# transistor_tester_V1_07_E3.net
KiCad netlist of a schematic drawn in Altium Designer
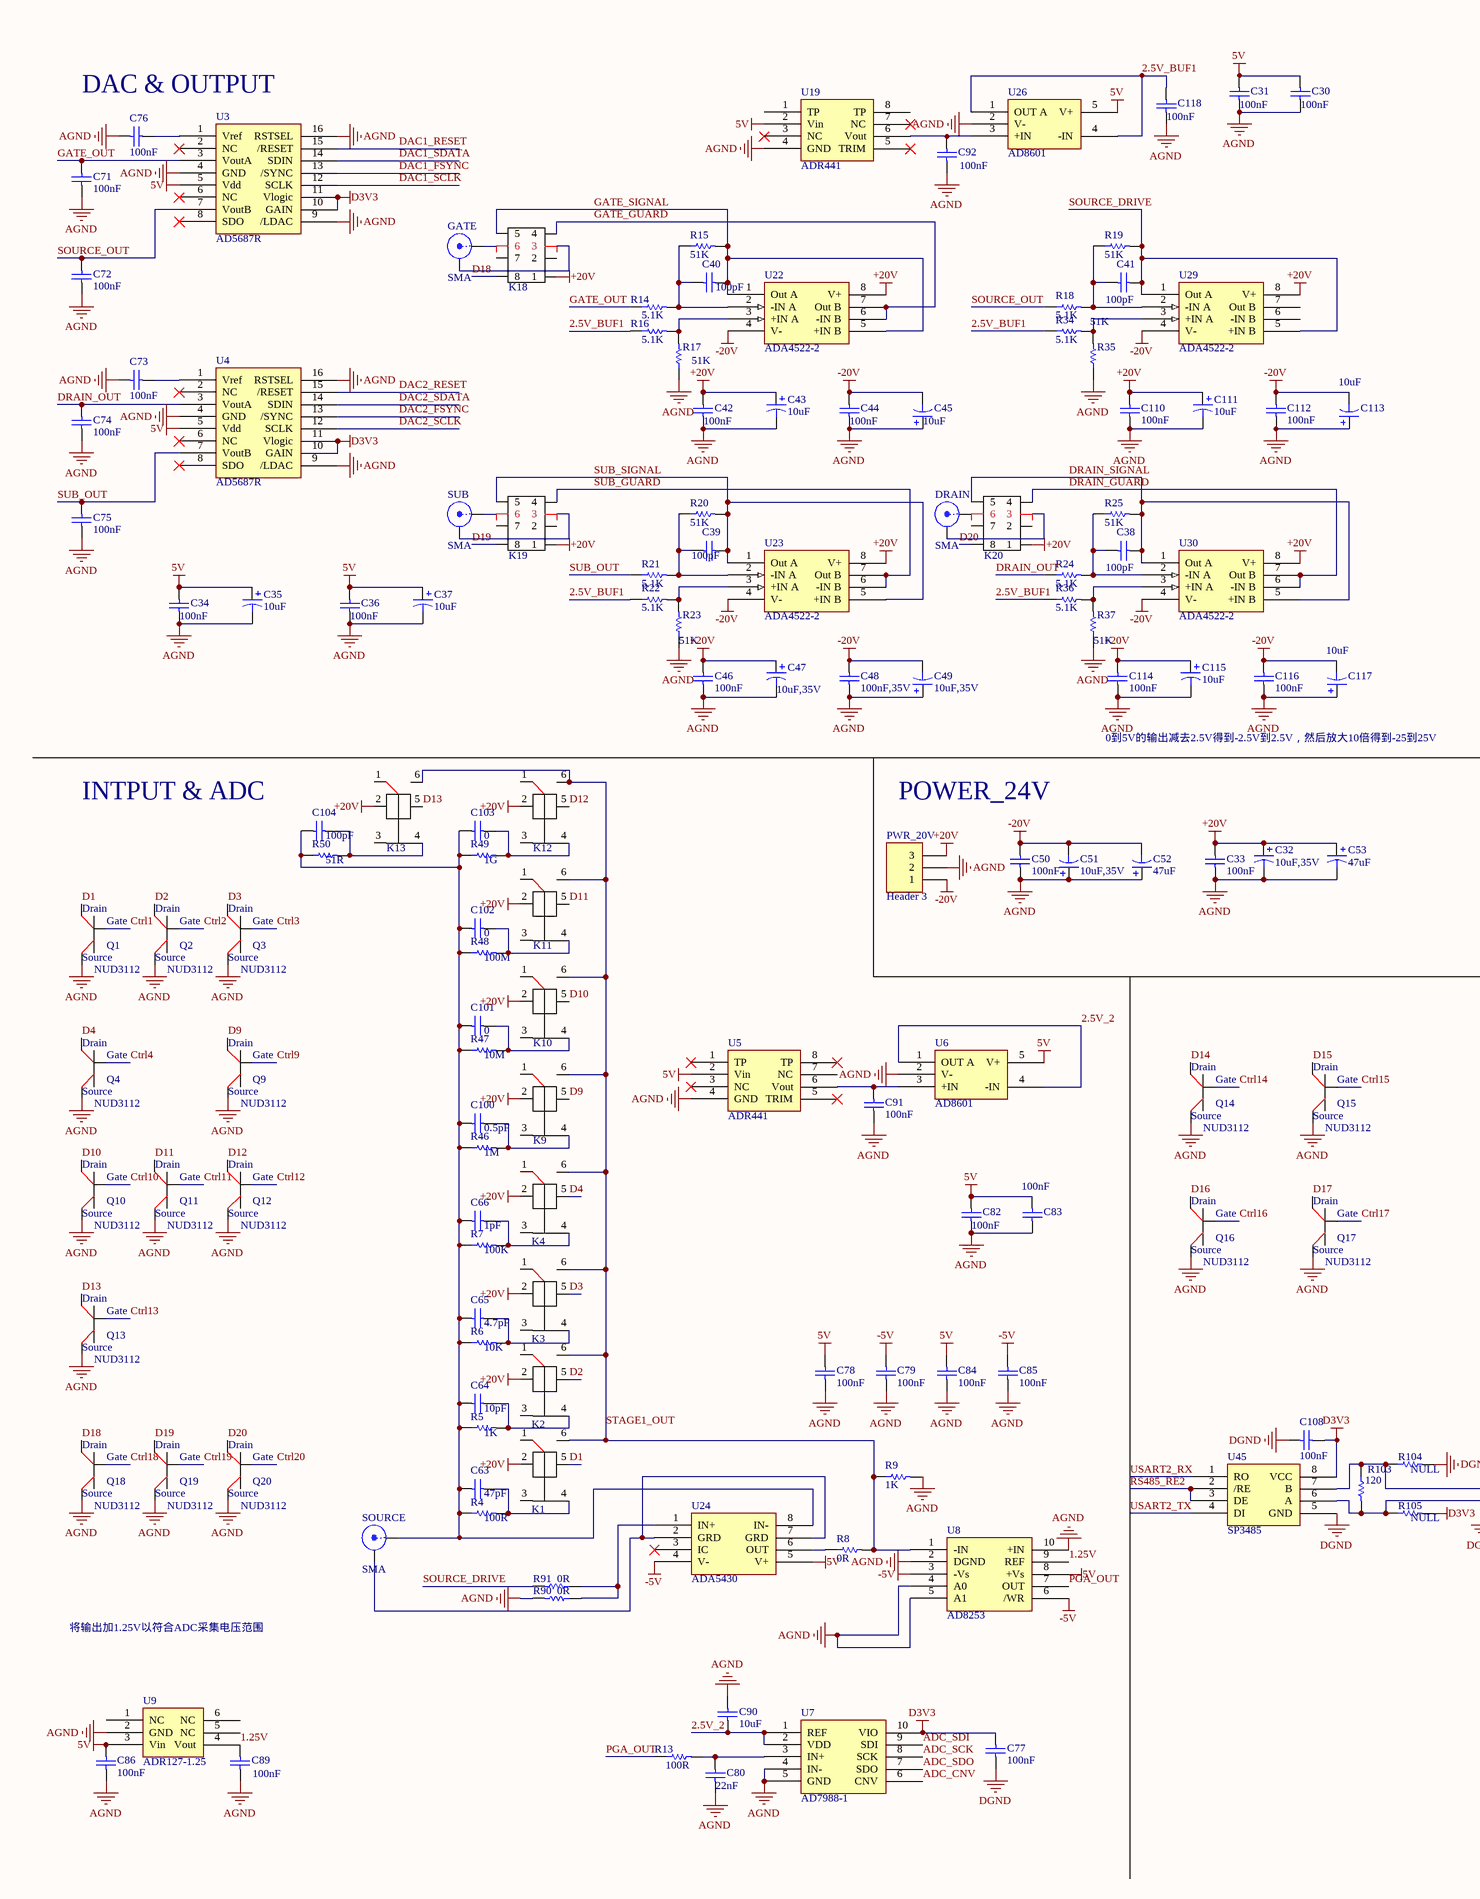
[diagram p0: transistor_tester_V1.07_E3.SchDoc, left]
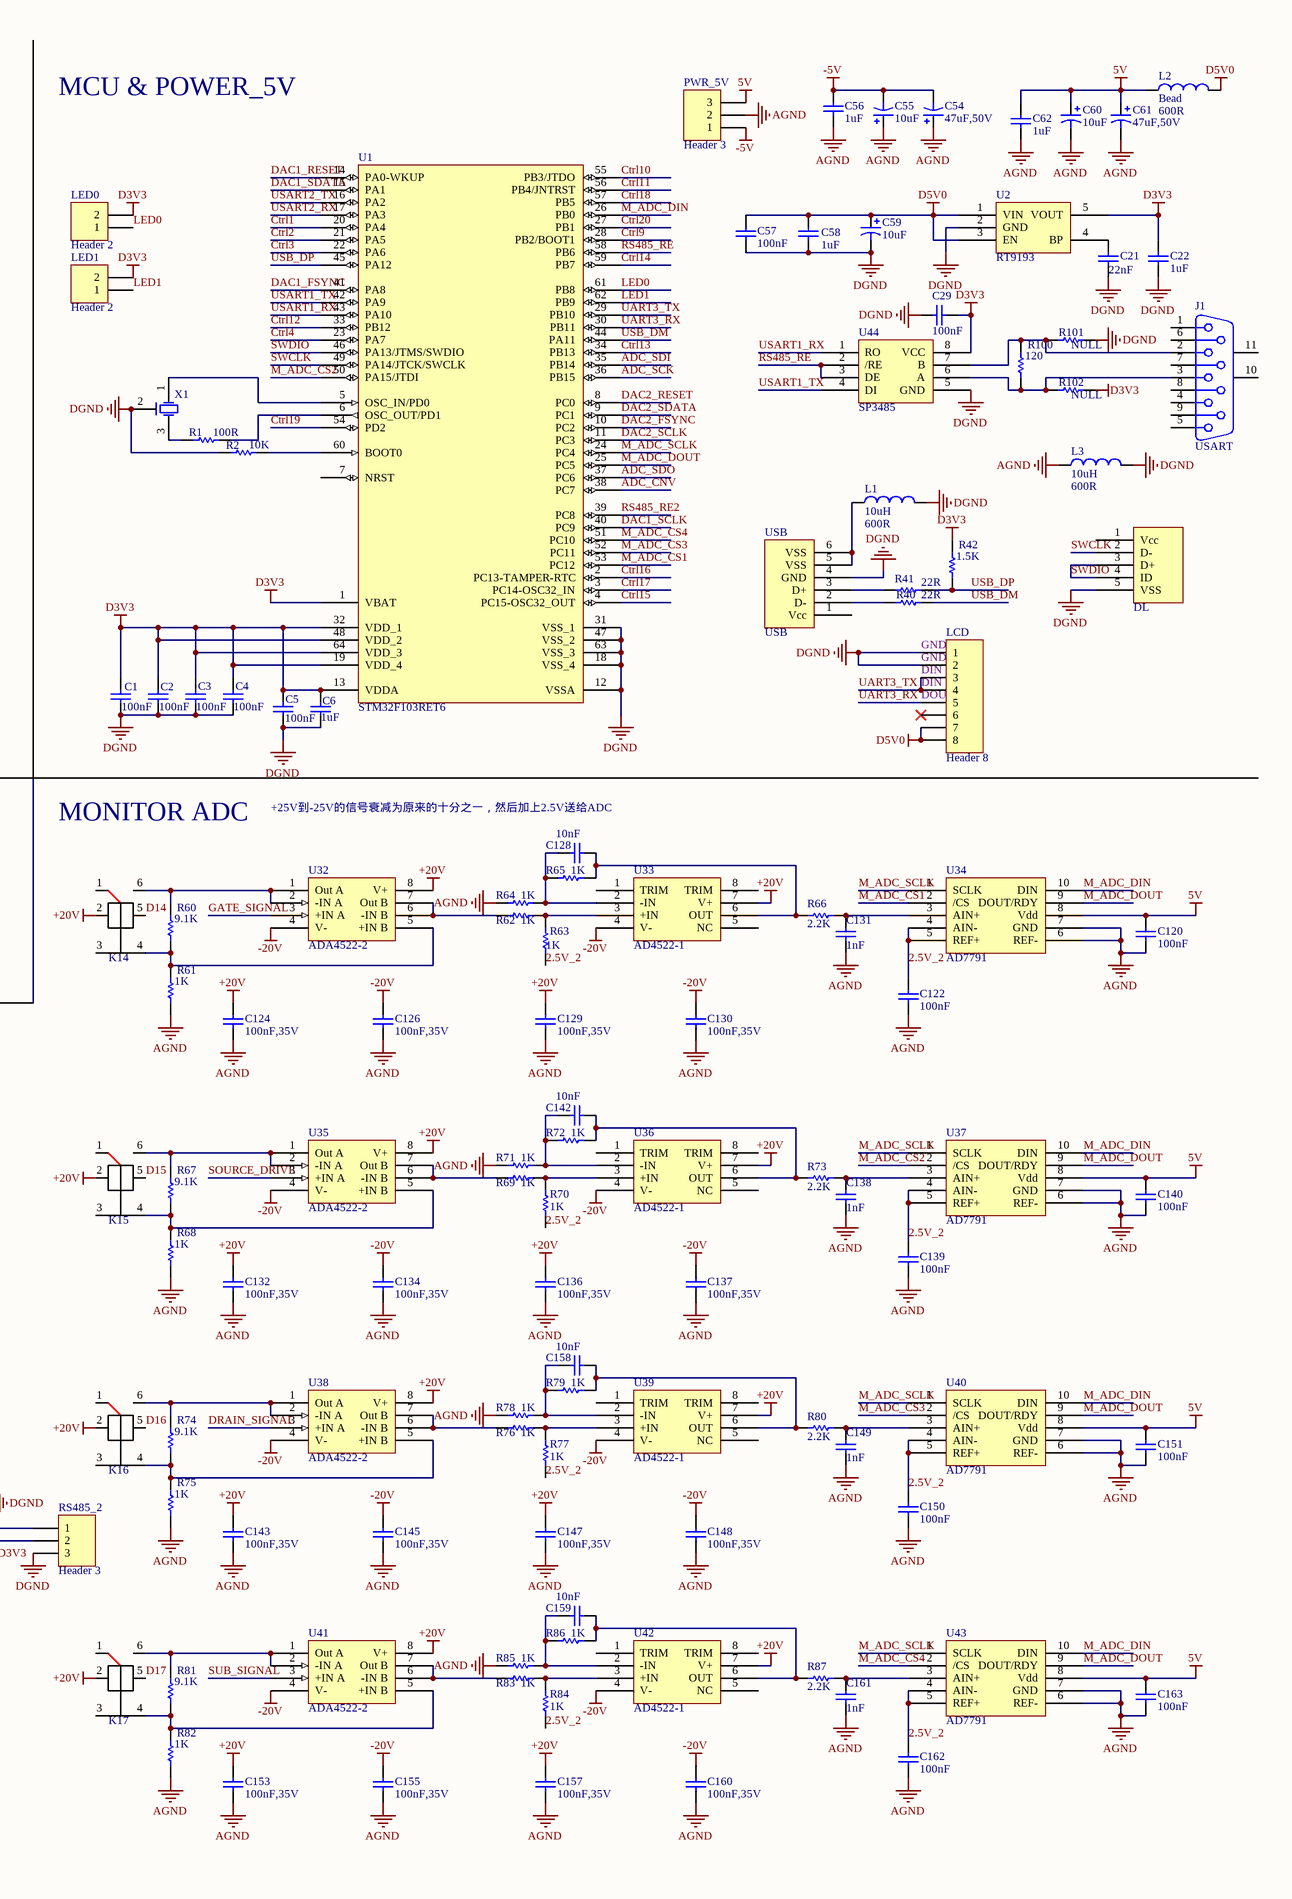
[diagram p1: transistor_tester_V1.07_E3.SchDoc, right]

(export (version "E")
  (design (tool "Eeschema 10.0.6"))
  (components
    (comp (ref "C1")
      (value "100nF")
      (footprint "BinFeng:0603")
      (description "Capacitor")
      (fields (field (name "PUBLISHER") "Altium Limited"))
      (libsource (lib "Miscellaneous Devices") (part "Cap"))
    )
    (comp (ref "C2")
      (value "100nF")
      (footprint "BinFeng:0603")
      (description "Capacitor")
      (fields (field (name "PUBLISHER") "Altium Limited"))
      (libsource (lib "Miscellaneous Devices") (part "Cap"))
    )
    (comp (ref "C3")
      (value "100nF")
      (footprint "BinFeng:0603")
      (description "Capacitor")
      (fields (field (name "PUBLISHER") "Altium Limited"))
      (libsource (lib "Miscellaneous Devices") (part "Cap"))
    )
    (comp (ref "C4")
      (value "100nF")
      (footprint "BinFeng:0603")
      (description "Capacitor")
      (fields (field (name "PUBLISHER") "Altium Limited"))
      (libsource (lib "Miscellaneous Devices") (part "Cap"))
    )
    (comp (ref "C5")
      (value "100nF")
      (footprint "BinFeng:0603")
      (description "Capacitor")
      (fields (field (name "PUBLISHER") "Altium Limited"))
      (libsource (lib "Miscellaneous Devices") (part "Cap"))
    )
    (comp (ref "C6")
      (value "1uF")
      (footprint "BinFeng:0603")
      (description "Capacitor")
      (fields (field (name "PUBLISHER") "Altium Limited"))
      (libsource (lib "Miscellaneous Devices") (part "Cap"))
    )
    (comp (ref "C21")
      (value "22nF")
      (footprint "BinFeng:0603")
      (description "Capacitor")
      (fields (field (name "PUBLISHER") "Altium Limited"))
      (libsource (lib "Miscellaneous Devices") (part "Cap"))
    )
    (comp (ref "C22")
      (value "1uF")
      (footprint "BinFeng:0603")
      (description "Capacitor")
      (fields (field (name "PUBLISHER") "Altium Limited"))
      (libsource (lib "Miscellaneous Devices") (part "Cap"))
    )
    (comp (ref "C29")
      (value "100nF")
      (footprint "BinFeng:0603")
      (description "Capacitor")
      (fields (field (name "PUBLISHER") "Altium Limited"))
      (libsource (lib "Miscellaneous Devices") (part "Cap"))
    )
    (comp (ref "C30")
      (value "100nF")
      (footprint "0805")
      (description "Capacitor")
      (fields (field (name "PUBLISHER") "Altium Limited"))
      (libsource (lib "Miscellaneous Devices") (part "Cap"))
    )
    (comp (ref "C31")
      (value "100nF")
      (footprint "0805")
      (description "Capacitor")
      (fields (field (name "PUBLISHER") "Altium Limited"))
      (libsource (lib "Miscellaneous Devices") (part "Cap"))
    )
    (comp (ref "C32")
      (value "10uF,35V")
      (footprint "6032_pol")
      (description "Polarized Capacitor (Radial)")
      (fields (field (name "Comment") "10uF") (field (name "PUBLISHER") "Altium Limited"))
      (libsource (lib "Miscellaneous Devices") (part "Cap Pol1"))
    )
    (comp (ref "C33")
      (value "100nF")
      (footprint "0805")
      (description "Capacitor")
      (fields (field (name "PUBLISHER") "Altium Limited"))
      (libsource (lib "Miscellaneous Devices") (part "Cap"))
    )
    (comp (ref "C34")
      (value "100nF")
      (footprint "0805")
      (description "Capacitor")
      (fields (field (name "PUBLISHER") "Altium Limited"))
      (libsource (lib "Miscellaneous Devices") (part "Cap"))
    )
    (comp (ref "C35")
      (value "10uF")
      (footprint "6032_pol")
      (description "Polarized Capacitor (Radial)")
      (fields (field (name "PUBLISHER") "Altium Limited"))
      (libsource (lib "Miscellaneous Devices") (part "Cap Pol1"))
    )
    (comp (ref "C36")
      (value "100nF")
      (footprint "0805")
      (description "Capacitor")
      (fields (field (name "PUBLISHER") "Altium Limited"))
      (libsource (lib "Miscellaneous Devices") (part "Cap"))
    )
    (comp (ref "C37")
      (value "10uF")
      (footprint "6032_pol")
      (description "Polarized Capacitor (Radial)")
      (fields (field (name "PUBLISHER") "Altium Limited"))
      (libsource (lib "Miscellaneous Devices") (part "Cap Pol1"))
    )
    (comp (ref "C38")
      (value "100pF")
      (footprint "0805")
      (description "Capacitor")
      (fields (field (name "PUBLISHER") "Altium Limited"))
      (libsource (lib "Miscellaneous Devices") (part "Cap"))
    )
    (comp (ref "C39")
      (value "100pF")
      (footprint "0805")
      (description "Capacitor")
      (fields (field (name "PUBLISHER") "Altium Limited"))
      (libsource (lib "Miscellaneous Devices") (part "Cap"))
    )
    (comp (ref "C40")
      (value "100pF")
      (footprint "0805")
      (description "Capacitor")
      (fields (field (name "PUBLISHER") "Altium Limited"))
      (libsource (lib "Miscellaneous Devices") (part "Cap"))
    )
    (comp (ref "C41")
      (value "100pF")
      (footprint "0805")
      (description "Capacitor")
      (fields (field (name "PUBLISHER") "Altium Limited"))
      (libsource (lib "Miscellaneous Devices") (part "Cap"))
    )
    (comp (ref "C42")
      (value "100nF")
      (footprint "0805")
      (description "Capacitor")
      (fields (field (name "PUBLISHER") "Altium Limited"))
      (libsource (lib "Miscellaneous Devices") (part "Cap"))
    )
    (comp (ref "C43")
      (value "10uF")
      (footprint "6032_pol")
      (description "Polarized Capacitor (Radial)")
      (fields (field (name "PUBLISHER") "Altium Limited"))
      (libsource (lib "Miscellaneous Devices") (part "Cap Pol1"))
    )
    (comp (ref "C44")
      (value "100nF")
      (footprint "0805")
      (description "Capacitor")
      (fields (field (name "PUBLISHER") "Altium Limited"))
      (libsource (lib "Miscellaneous Devices") (part "Cap"))
    )
    (comp (ref "C45")
      (value "10uF")
      (footprint "6032_pol")
      (description "Polarized Capacitor (Radial)")
      (fields (field (name "PUBLISHER") "Altium Limited"))
      (libsource (lib "Miscellaneous Devices") (part "Cap Pol1"))
    )
    (comp (ref "C46")
      (value "100nF")
      (footprint "0805")
      (description "Capacitor")
      (fields (field (name "PUBLISHER") "Altium Limited"))
      (libsource (lib "Miscellaneous Devices") (part "Cap"))
    )
    (comp (ref "C47")
      (value "10uF,35V")
      (footprint "6032_pol")
      (description "Polarized Capacitor (Radial)")
      (fields (field (name "Comment") "10uF") (field (name "PUBLISHER") "Altium Limited"))
      (libsource (lib "Miscellaneous Devices") (part "Cap Pol1"))
    )
    (comp (ref "C48")
      (value "100nF,35V")
      (footprint "0805")
      (description "Capacitor")
      (fields (field (name "Comment") "100nF") (field (name "PUBLISHER") "Altium Limited"))
      (libsource (lib "Miscellaneous Devices") (part "Cap"))
    )
    (comp (ref "C49")
      (value "10uF,35V")
      (footprint "6032_pol")
      (description "Polarized Capacitor (Radial)")
      (fields (field (name "Comment") "10uF") (field (name "PUBLISHER") "Altium Limited"))
      (libsource (lib "Miscellaneous Devices") (part "Cap Pol1"))
    )
    (comp (ref "C50")
      (value "100nF")
      (footprint "0805")
      (description "Capacitor")
      (fields (field (name "PUBLISHER") "Altium Limited"))
      (libsource (lib "Miscellaneous Devices") (part "Cap"))
    )
    (comp (ref "C51")
      (value "10uF,35V")
      (footprint "6032_pol")
      (description "Polarized Capacitor (Radial)")
      (fields (field (name "Comment") "10uF") (field (name "PUBLISHER") "Altium Limited"))
      (libsource (lib "Miscellaneous Devices") (part "Cap Pol1"))
    )
    (comp (ref "C52")
      (value "47uF")
      (footprint "cap_pol_8*10.2")
      (description "Polarized Capacitor (Radial)")
      (fields (field (name "PUBLISHER") "Altium Limited"))
      (libsource (lib "Miscellaneous Devices") (part "Cap Pol1"))
    )
    (comp (ref "C53")
      (value "47uF")
      (footprint "cap_pol_8*10.2")
      (description "Polarized Capacitor (Radial)")
      (fields (field (name "PUBLISHER") "Altium Limited"))
      (libsource (lib "Miscellaneous Devices") (part "Cap Pol1"))
    )
    (comp (ref "C54")
      (value "47uF,50V")
      (footprint "cap_pol_8*10.2")
      (description "Polarized Capacitor (Radial)")
      (fields (field (name "PUBLISHER") "Altium Limited"))
      (libsource (lib "Miscellaneous Devices") (part "Cap Pol1"))
    )
    (comp (ref "C55")
      (value "10uF")
      (footprint "6032_pol")
      (description "Polarized Capacitor (Radial)")
      (fields (field (name "PUBLISHER") "Altium Limited"))
      (libsource (lib "Miscellaneous Devices") (part "Cap Pol1"))
    )
    (comp (ref "C56")
      (value "1uF")
      (footprint "0805")
      (description "Capacitor,100V")
      (fields (field (name "PUBLISHER") "Altium Limited"))
      (libsource (lib "Miscellaneous Devices") (part "Cap"))
    )
    (comp (ref "C57")
      (value "100nF")
      (footprint "0805")
      (description "Capacitor,100V")
      (fields (field (name "PUBLISHER") "Altium Limited"))
      (libsource (lib "Miscellaneous Devices") (part "Cap"))
    )
    (comp (ref "C58")
      (value "1uF")
      (footprint "0805")
      (description "Capacitor")
      (fields (field (name "PUBLISHER") "Altium Limited"))
      (libsource (lib "Miscellaneous Devices") (part "Cap"))
    )
    (comp (ref "C59")
      (value "10uF")
      (footprint "6032_pol")
      (description "Polarized Capacitor (Radial)")
      (fields (field (name "PUBLISHER") "Altium Limited"))
      (libsource (lib "Miscellaneous Devices") (part "Cap Pol1"))
    )
    (comp (ref "C60")
      (value "10uF")
      (footprint "6032_pol")
      (description "Polarized Capacitor (Radial)")
      (fields (field (name "PUBLISHER") "Altium Limited"))
      (libsource (lib "Miscellaneous Devices") (part "Cap Pol1"))
    )
    (comp (ref "C61")
      (value "47uF,50V")
      (footprint "cap_pol_8*10.2")
      (description "Polarized Capacitor (Radial)")
      (fields (field (name "PUBLISHER") "Altium Limited"))
      (libsource (lib "Miscellaneous Devices") (part "Cap Pol1"))
    )
    (comp (ref "C62")
      (value "1uF")
      (footprint "0805")
      (description "Capacitor,100V")
      (fields (field (name "PUBLISHER") "Altium Limited"))
      (libsource (lib "Miscellaneous Devices") (part "Cap"))
    )
    (comp (ref "C63")
      (value "47pF")
      (footprint "0805")
      (description "Capacitor")
      (fields (field (name "PUBLISHER") "Altium Limited"))
      (libsource (lib "Miscellaneous Devices") (part "Cap"))
    )
    (comp (ref "C64")
      (value "10pF")
      (footprint "0805")
      (description "Capacitor")
      (fields (field (name "PUBLISHER") "Altium Limited"))
      (libsource (lib "Miscellaneous Devices") (part "Cap"))
    )
    (comp (ref "C65")
      (value "4.7pF")
      (footprint "0805")
      (description "Capacitor")
      (fields (field (name "Comment") "5pF") (field (name "PUBLISHER") "Altium Limited"))
      (libsource (lib "Miscellaneous Devices") (part "Cap"))
    )
    (comp (ref "C66")
      (value "1pF")
      (footprint "0805")
      (description "Capacitor")
      (fields (field (name "PUBLISHER") "Altium Limited"))
      (libsource (lib "Miscellaneous Devices") (part "Cap"))
    )
    (comp (ref "C71")
      (value "100nF")
      (footprint "BinFeng:0603")
      (description "Capacitor")
      (fields (field (name "PUBLISHER") "Altium Limited"))
      (libsource (lib "Miscellaneous Devices") (part "Cap"))
    )
    (comp (ref "C72")
      (value "100nF")
      (footprint "BinFeng:0603")
      (description "Capacitor")
      (fields (field (name "PUBLISHER") "Altium Limited"))
      (libsource (lib "Miscellaneous Devices") (part "Cap"))
    )
    (comp (ref "C73")
      (value "100nF")
      (footprint "BinFeng:0603")
      (description "Capacitor")
      (fields (field (name "PUBLISHER") "Altium Limited"))
      (libsource (lib "Miscellaneous Devices") (part "Cap"))
    )
    (comp (ref "C74")
      (value "100nF")
      (footprint "BinFeng:0603")
      (description "Capacitor")
      (fields (field (name "PUBLISHER") "Altium Limited"))
      (libsource (lib "Miscellaneous Devices") (part "Cap"))
    )
    (comp (ref "C75")
      (value "100nF")
      (footprint "BinFeng:0603")
      (description "Capacitor")
      (fields (field (name "PUBLISHER") "Altium Limited"))
      (libsource (lib "Miscellaneous Devices") (part "Cap"))
    )
    (comp (ref "C76")
      (value "100nF")
      (footprint "BinFeng:0603")
      (description "Capacitor")
      (fields (field (name "PUBLISHER") "Altium Limited"))
      (libsource (lib "Miscellaneous Devices") (part "Cap"))
    )
    (comp (ref "C77")
      (value "100nF")
      (footprint "0805")
      (description "Capacitor,100V")
      (fields (field (name "PUBLISHER") "Altium Limited"))
      (libsource (lib "Miscellaneous Devices") (part "Cap"))
    )
    (comp (ref "C78")
      (value "100nF")
      (footprint "BinFeng:0603")
      (description "Capacitor")
      (fields (field (name "PUBLISHER") "Altium Limited"))
      (libsource (lib "Miscellaneous Devices") (part "Cap"))
    )
    (comp (ref "C79")
      (value "100nF")
      (footprint "BinFeng:0603")
      (description "Capacitor")
      (fields (field (name "PUBLISHER") "Altium Limited"))
      (libsource (lib "Miscellaneous Devices") (part "Cap"))
    )
    (comp (ref "C80")
      (value "22nF")
      (footprint "BinFeng:0603")
      (description "Capacitor")
      (fields (field (name "PUBLISHER") "Altium Limited"))
      (libsource (lib "Miscellaneous Devices") (part "Cap"))
    )
    (comp (ref "C82")
      (value "100nF")
      (footprint "BinFeng:0603")
      (description "Capacitor")
      (fields (field (name "PUBLISHER") "Altium Limited"))
      (libsource (lib "Miscellaneous Devices") (part "Cap"))
    )
    (comp (ref "C83")
      (value "100nF")
      (footprint "0805")
      (description "Capacitor")
      (fields (field (name "PUBLISHER") "Altium Limited"))
      (libsource (lib "Miscellaneous Devices") (part "Cap"))
    )
    (comp (ref "C84")
      (value "100nF")
      (footprint "0805")
      (description "Capacitor")
      (fields (field (name "PUBLISHER") "Altium Limited"))
      (libsource (lib "Miscellaneous Devices") (part "Cap"))
    )
    (comp (ref "C85")
      (value "100nF")
      (footprint "0805")
      (description "Capacitor")
      (fields (field (name "PUBLISHER") "Altium Limited"))
      (libsource (lib "Miscellaneous Devices") (part "Cap"))
    )
    (comp (ref "C86")
      (value "100nF")
      (footprint "BinFeng:0603")
      (description "Capacitor")
      (fields (field (name "PUBLISHER") "Altium Limited"))
      (libsource (lib "Miscellaneous Devices") (part "Cap"))
    )
    (comp (ref "C89")
      (value "100nF")
      (footprint "BinFeng:0603")
      (description "Capacitor")
      (fields (field (name "PUBLISHER") "Altium Limited"))
      (libsource (lib "Miscellaneous Devices") (part "Cap"))
    )
    (comp (ref "C90")
      (value "10uF")
      (footprint "0805")
      (description "Capacitor")
      (fields (field (name "PUBLISHER") "Altium Limited"))
      (libsource (lib "Miscellaneous Devices") (part "Cap"))
    )
    (comp (ref "C91")
      (value "100nF")
      (footprint "0805")
      (description "Capacitor")
      (fields (field (name "PUBLISHER") "Altium Limited"))
      (libsource (lib "Miscellaneous Devices") (part "Cap"))
    )
    (comp (ref "C92")
      (value "100nF")
      (footprint "0805")
      (description "Capacitor")
      (fields (field (name "PUBLISHER") "Altium Limited"))
      (libsource (lib "Miscellaneous Devices") (part "Cap"))
    )
    (comp (ref "C100")
      (value "0.5pF")
      (footprint "0805")
      (description "Capacitor")
      (fields (field (name "PUBLISHER") "Altium Limited"))
      (libsource (lib "Miscellaneous Devices") (part "Cap"))
    )
    (comp (ref "C101")
      (value "0")
      (footprint "0805")
      (description "Capacitor")
      (fields (field (name "Comment") "NULL") (field (name "PUBLISHER") "Altium Limited"))
      (libsource (lib "Miscellaneous Devices") (part "Cap"))
    )
    (comp (ref "C102")
      (value "0")
      (footprint "0805")
      (description "Capacitor")
      (fields (field (name "Comment") "NULL") (field (name "PUBLISHER") "Altium Limited"))
      (libsource (lib "Miscellaneous Devices") (part "Cap"))
    )
    (comp (ref "C103")
      (value "0")
      (footprint "0805")
      (description "Capacitor")
      (fields (field (name "Comment") "NULL") (field (name "PUBLISHER") "Altium Limited"))
      (libsource (lib "Miscellaneous Devices") (part "Cap"))
    )
    (comp (ref "C104")
      (value "100pF")
      (footprint "0805")
      (description "Capacitor")
      (fields (field (name "PUBLISHER") "Altium Limited"))
      (libsource (lib "Miscellaneous Devices") (part "Cap"))
    )
    (comp (ref "C108")
      (value "100nF")
      (footprint "BinFeng:0603")
      (description "Capacitor")
      (fields (field (name "PUBLISHER") "Altium Limited"))
      (libsource (lib "Miscellaneous Devices") (part "Cap"))
    )
    (comp (ref "C110")
      (value "100nF")
      (footprint "0805")
      (description "Capacitor")
      (fields (field (name "PUBLISHER") "Altium Limited"))
      (libsource (lib "Miscellaneous Devices") (part "Cap"))
    )
    (comp (ref "C111")
      (value "10uF")
      (footprint "6032_pol")
      (description "Polarized Capacitor (Radial)")
      (fields (field (name "PUBLISHER") "Altium Limited"))
      (libsource (lib "Miscellaneous Devices") (part "Cap Pol1"))
    )
    (comp (ref "C112")
      (value "100nF")
      (footprint "0805")
      (description "Capacitor")
      (fields (field (name "PUBLISHER") "Altium Limited"))
      (libsource (lib "Miscellaneous Devices") (part "Cap"))
    )
    (comp (ref "C113")
      (value "10uF")
      (footprint "6032_pol")
      (description "Polarized Capacitor (Radial)")
      (fields (field (name "PUBLISHER") "Altium Limited"))
      (libsource (lib "Miscellaneous Devices") (part "Cap Pol1"))
    )
    (comp (ref "C114")
      (value "100nF")
      (footprint "0805")
      (description "Capacitor")
      (fields (field (name "PUBLISHER") "Altium Limited"))
      (libsource (lib "Miscellaneous Devices") (part "Cap"))
    )
    (comp (ref "C115")
      (value "10uF")
      (footprint "6032_pol")
      (description "Polarized Capacitor (Radial)")
      (fields (field (name "PUBLISHER") "Altium Limited"))
      (libsource (lib "Miscellaneous Devices") (part "Cap Pol1"))
    )
    (comp (ref "C116")
      (value "100nF")
      (footprint "0805")
      (description "Capacitor")
      (fields (field (name "PUBLISHER") "Altium Limited"))
      (libsource (lib "Miscellaneous Devices") (part "Cap"))
    )
    (comp (ref "C117")
      (value "10uF")
      (footprint "6032_pol")
      (description "Polarized Capacitor (Radial)")
      (fields (field (name "PUBLISHER") "Altium Limited"))
      (libsource (lib "Miscellaneous Devices") (part "Cap Pol1"))
    )
    (comp (ref "C118")
      (value "100nF")
      (footprint "0805")
      (description "Capacitor")
      (fields (field (name "PUBLISHER") "Altium Limited"))
      (libsource (lib "Miscellaneous Devices") (part "Cap"))
    )
    (comp (ref "C120")
      (value "100nF")
      (footprint "0805")
      (description "Capacitor,100V")
      (fields (field (name "PUBLISHER") "Altium Limited"))
      (libsource (lib "Miscellaneous Devices") (part "Cap"))
    )
    (comp (ref "C122")
      (value "100nF")
      (footprint "0805")
      (description "Capacitor,100V")
      (fields (field (name "PUBLISHER") "Altium Limited"))
      (libsource (lib "Miscellaneous Devices") (part "Cap"))
    )
    (comp (ref "C124")
      (value "100nF,35V")
      (footprint "0805")
      (description "Capacitor")
      (fields (field (name "Comment") "100nF") (field (name "PUBLISHER") "Altium Limited"))
      (libsource (lib "Miscellaneous Devices") (part "Cap"))
    )
    (comp (ref "C126")
      (value "100nF,35V")
      (footprint "0805")
      (description "Capacitor")
      (fields (field (name "Comment") "100nF") (field (name "PUBLISHER") "Altium Limited"))
      (libsource (lib "Miscellaneous Devices") (part "Cap"))
    )
    (comp (ref "C128")
      (value "10nF")
      (footprint "BinFeng:0603")
      (description "Capacitor")
      (fields (field (name "PUBLISHER") "Altium Limited"))
      (libsource (lib "Miscellaneous Devices") (part "Cap"))
    )
    (comp (ref "C129")
      (value "100nF,35V")
      (footprint "0805")
      (description "Capacitor")
      (fields (field (name "Comment") "100nF") (field (name "PUBLISHER") "Altium Limited"))
      (libsource (lib "Miscellaneous Devices") (part "Cap"))
    )
    (comp (ref "C130")
      (value "100nF,35V")
      (footprint "0805")
      (description "Capacitor")
      (fields (field (name "Comment") "100nF") (field (name "PUBLISHER") "Altium Limited"))
      (libsource (lib "Miscellaneous Devices") (part "Cap"))
    )
    (comp (ref "C131")
      (value "1nF")
      (footprint "BinFeng:0603")
      (description "Capacitor,100V")
      (fields (field (name "PUBLISHER") "Altium Limited"))
      (libsource (lib "Miscellaneous Devices") (part "Cap"))
    )
    (comp (ref "C132")
      (value "100nF,35V")
      (footprint "0805")
      (description "Capacitor")
      (fields (field (name "Comment") "100nF") (field (name "PUBLISHER") "Altium Limited"))
      (libsource (lib "Miscellaneous Devices") (part "Cap"))
    )
    (comp (ref "C134")
      (value "100nF,35V")
      (footprint "0805")
      (description "Capacitor")
      (fields (field (name "Comment") "100nF") (field (name "PUBLISHER") "Altium Limited"))
      (libsource (lib "Miscellaneous Devices") (part "Cap"))
    )
    (comp (ref "C136")
      (value "100nF,35V")
      (footprint "0805")
      (description "Capacitor")
      (fields (field (name "Comment") "100nF") (field (name "PUBLISHER") "Altium Limited"))
      (libsource (lib "Miscellaneous Devices") (part "Cap"))
    )
    (comp (ref "C137")
      (value "100nF,35V")
      (footprint "0805")
      (description "Capacitor")
      (fields (field (name "Comment") "100nF") (field (name "PUBLISHER") "Altium Limited"))
      (libsource (lib "Miscellaneous Devices") (part "Cap"))
    )
    (comp (ref "C138")
      (value "1nF")
      (footprint "BinFeng:0603")
      (description "Capacitor,100V")
      (fields (field (name "PUBLISHER") "Altium Limited"))
      (libsource (lib "Miscellaneous Devices") (part "Cap"))
    )
    (comp (ref "C139")
      (value "100nF")
      (footprint "0805")
      (description "Capacitor,100V")
      (fields (field (name "PUBLISHER") "Altium Limited"))
      (libsource (lib "Miscellaneous Devices") (part "Cap"))
    )
    (comp (ref "C140")
      (value "100nF")
      (footprint "0805")
      (description "Capacitor,100V")
      (fields (field (name "PUBLISHER") "Altium Limited"))
      (libsource (lib "Miscellaneous Devices") (part "Cap"))
    )
    (comp (ref "C142")
      (value "10nF")
      (footprint "BinFeng:0603")
      (description "Capacitor")
      (fields (field (name "PUBLISHER") "Altium Limited"))
      (libsource (lib "Miscellaneous Devices") (part "Cap"))
    )
    (comp (ref "C143")
      (value "100nF,35V")
      (footprint "0805")
      (description "Capacitor")
      (fields (field (name "Comment") "100nF") (field (name "PUBLISHER") "Altium Limited"))
      (libsource (lib "Miscellaneous Devices") (part "Cap"))
    )
    (comp (ref "C145")
      (value "100nF,35V")
      (footprint "0805")
      (description "Capacitor")
      (fields (field (name "Comment") "100nF") (field (name "PUBLISHER") "Altium Limited"))
      (libsource (lib "Miscellaneous Devices") (part "Cap"))
    )
    (comp (ref "C147")
      (value "100nF,35V")
      (footprint "0805")
      (description "Capacitor")
      (fields (field (name "Comment") "100nF") (field (name "PUBLISHER") "Altium Limited"))
      (libsource (lib "Miscellaneous Devices") (part "Cap"))
    )
    (comp (ref "C148")
      (value "100nF,35V")
      (footprint "0805")
      (description "Capacitor")
      (fields (field (name "Comment") "100nF") (field (name "PUBLISHER") "Altium Limited"))
      (libsource (lib "Miscellaneous Devices") (part "Cap"))
    )
    (comp (ref "C149")
      (value "1nF")
      (footprint "BinFeng:0603")
      (description "Capacitor,100V")
      (fields (field (name "PUBLISHER") "Altium Limited"))
      (libsource (lib "Miscellaneous Devices") (part "Cap"))
    )
    (comp (ref "C150")
      (value "100nF")
      (footprint "0805")
      (description "Capacitor,100V")
      (fields (field (name "PUBLISHER") "Altium Limited"))
      (libsource (lib "Miscellaneous Devices") (part "Cap"))
    )
    (comp (ref "C151")
      (value "100nF")
      (footprint "0805")
      (description "Capacitor,100V")
      (fields (field (name "PUBLISHER") "Altium Limited"))
      (libsource (lib "Miscellaneous Devices") (part "Cap"))
    )
    (comp (ref "C153")
      (value "100nF,35V")
      (footprint "0805")
      (description "Capacitor")
      (fields (field (name "Comment") "100nF") (field (name "PUBLISHER") "Altium Limited"))
      (libsource (lib "Miscellaneous Devices") (part "Cap"))
    )
    (comp (ref "C155")
      (value "100nF,35V")
      (footprint "0805")
      (description "Capacitor")
      (fields (field (name "Comment") "100nF") (field (name "PUBLISHER") "Altium Limited"))
      (libsource (lib "Miscellaneous Devices") (part "Cap"))
    )
    (comp (ref "C157")
      (value "100nF,35V")
      (footprint "0805")
      (description "Capacitor")
      (fields (field (name "Comment") "100nF") (field (name "PUBLISHER") "Altium Limited"))
      (libsource (lib "Miscellaneous Devices") (part "Cap"))
    )
    (comp (ref "C158")
      (value "10nF")
      (footprint "BinFeng:0603")
      (description "Capacitor")
      (fields (field (name "PUBLISHER") "Altium Limited"))
      (libsource (lib "Miscellaneous Devices") (part "Cap"))
    )
    (comp (ref "C159")
      (value "10nF")
      (footprint "BinFeng:0603")
      (description "Capacitor")
      (fields (field (name "PUBLISHER") "Altium Limited"))
      (libsource (lib "Miscellaneous Devices") (part "Cap"))
    )
    (comp (ref "C160")
      (value "100nF,35V")
      (footprint "0805")
      (description "Capacitor")
      (fields (field (name "Comment") "100nF") (field (name "PUBLISHER") "Altium Limited"))
      (libsource (lib "Miscellaneous Devices") (part "Cap"))
    )
    (comp (ref "C161")
      (value "1nF")
      (footprint "BinFeng:0603")
      (description "Capacitor,100V")
      (fields (field (name "PUBLISHER") "Altium Limited"))
      (libsource (lib "Miscellaneous Devices") (part "Cap"))
    )
    (comp (ref "C162")
      (value "100nF")
      (footprint "0805")
      (description "Capacitor,100V")
      (fields (field (name "PUBLISHER") "Altium Limited"))
      (libsource (lib "Miscellaneous Devices") (part "Cap"))
    )
    (comp (ref "C163")
      (value "100nF")
      (footprint "0805")
      (description "Capacitor,100V")
      (fields (field (name "PUBLISHER") "Altium Limited"))
      (libsource (lib "Miscellaneous Devices") (part "Cap"))
    )
    (comp (ref "DL")
      (value "USB_5pin")
      (footprint "USBmicro_B")
      (libsource (lib "BinFeng_Connectors") (part "USB_5pin"))
    )
    (comp (ref "DRAIN")
      (value "SMA")
      (footprint "SMA")
      (description "BNC Elbow Connector")
      (fields (field (name "PUBLISHER") "Altium Limited"))
      (libsource (lib "Miscellaneous Connectors") (part "BNC"))
    )
    (comp (ref "GATE")
      (value "SMA")
      (footprint "SMA")
      (description "BNC Elbow Connector")
      (fields (field (name "PUBLISHER") "Altium Limited"))
      (libsource (lib "Miscellaneous Connectors") (part "BNC"))
    )
    (comp (ref "J1")
      (value "USART")
      (footprint "DSUB1.385-2H9")
      (description "Receptacle Assembly, 9 Position, Right Angle")
      (fields (field (name "PUBLISHER") "Altium Limited"))
      (libsource (lib "Miscellaneous Connectors") (part "D Connector 9"))
    )
    (comp (ref "K1")
      (value "Relay")
      (footprint "Relay_OMRON5V")
      (description "Relay OMRON")
      (libsource (lib "BinFeng_IC") (part "Relay_OMRON5V"))
    )
    (comp (ref "K2")
      (value "Relay")
      (footprint "Relay_OMRON5V")
      (description "Relay OMRON")
      (libsource (lib "BinFeng_IC") (part "Relay_OMRON5V"))
    )
    (comp (ref "K3")
      (value "Relay")
      (footprint "Relay_OMRON5V")
      (description "Relay OMRON")
      (libsource (lib "BinFeng_IC") (part "Relay_OMRON5V"))
    )
    (comp (ref "K4")
      (value "Relay")
      (footprint "Relay_OMRON5V")
      (description "Relay OMRON")
      (libsource (lib "BinFeng_IC") (part "Relay_OMRON5V"))
    )
    (comp (ref "K9")
      (value "Relay")
      (footprint "Relay_OMRON5V")
      (description "Relay OMRON")
      (libsource (lib "BinFeng_IC") (part "Relay_OMRON5V"))
    )
    (comp (ref "K10")
      (value "Relay")
      (footprint "Relay_OMRON5V")
      (description "Relay OMRON")
      (libsource (lib "BinFeng_IC") (part "Relay_OMRON5V"))
    )
    (comp (ref "K11")
      (value "Relay")
      (footprint "Relay_OMRON5V")
      (description "Relay OMRON")
      (libsource (lib "BinFeng_IC") (part "Relay_OMRON5V"))
    )
    (comp (ref "K12")
      (value "Relay")
      (footprint "Relay_OMRON5V")
      (description "Relay OMRON")
      (libsource (lib "BinFeng_IC") (part "Relay_OMRON5V"))
    )
    (comp (ref "K13")
      (value "Relay")
      (footprint "Relay_OMRON5V")
      (description "Relay OMRON")
      (libsource (lib "BinFeng_IC") (part "Relay_OMRON5V"))
    )
    (comp (ref "K14")
      (value "Relay")
      (footprint "Relay_OMRON5V")
      (description "Relay OMRON")
      (libsource (lib "BinFeng_IC") (part "Relay_OMRON5V"))
    )
    (comp (ref "K15")
      (value "Relay")
      (footprint "Relay_OMRON5V")
      (description "Relay OMRON")
      (libsource (lib "BinFeng_IC") (part "Relay_OMRON5V"))
    )
    (comp (ref "K16")
      (value "Relay")
      (footprint "Relay_OMRON5V")
      (description "Relay OMRON")
      (libsource (lib "BinFeng_IC") (part "Relay_OMRON5V"))
    )
    (comp (ref "K17")
      (value "Relay")
      (footprint "Relay_OMRON5V")
      (description "Relay OMRON")
      (libsource (lib "BinFeng_IC") (part "Relay_OMRON5V"))
    )
    (comp (ref "K18")
      (value "AXICOM IM")
      (footprint "AXICOM_IM06")
      (libsource (lib "BinFeng_IC") (part "AXiCOM IM05"))
    )
    (comp (ref "K19")
      (value "AXICOM IM")
      (footprint "AXICOM_IM06")
      (libsource (lib "BinFeng_IC") (part "AXiCOM IM05"))
    )
    (comp (ref "K20")
      (value "AXICOM IM")
      (footprint "AXICOM_IM06")
      (libsource (lib "BinFeng_IC") (part "AXiCOM IM05"))
    )
    (comp (ref "L1")
      (value "10uH")
      (footprint "0805")
      (description "Inductor")
      (fields (field (name "ALTIUM_VALUE") "600R") (field (name "PUBLISHER") "Altium Limited"))
      (libsource (lib "Miscellaneous Devices") (part "Inductor"))
    )
    (comp (ref "L2")
      (value "Bead")
      (footprint "8040")
      (description "Inductor")
      (fields (field (name "ALTIUM_VALUE") "600R") (field (name "PUBLISHER") "Altium Limited"))
      (libsource (lib "Miscellaneous Devices") (part "Inductor"))
    )
    (comp (ref "L3")
      (value "10uH")
      (footprint "1206")
      (description "Inductor")
      (fields (field (name "ALTIUM_VALUE") "600R") (field (name "PUBLISHER") "Altium Limited"))
      (libsource (lib "Miscellaneous Devices") (part "Inductor"))
    )
    (comp (ref "LCD")
      (value "Header 8")
      (footprint "HDR1X8")
      (description "Header, 8-Pin")
      (fields (field (name "PUBLISHER") "Altium Limited"))
      (libsource (lib "Miscellaneous Connectors") (part "Header 8"))
    )
    (comp (ref "LED0")
      (value "Header 2")
      (footprint "HDR1X2")
      (description "Header, 2-Pin")
      (fields (field (name "PUBLISHER") "Altium Limited"))
      (libsource (lib "Miscellaneous Connectors") (part "Header 2"))
    )
    (comp (ref "LED1")
      (value "Header 2")
      (footprint "HDR1X2")
      (description "Header, 2-Pin")
      (fields (field (name "PUBLISHER") "Altium Limited"))
      (libsource (lib "Miscellaneous Connectors") (part "Header 2"))
    )
    (comp (ref "PWR_5V")
      (value "Header 3")
      (footprint "PWR_3T")
      (description "Header, 3-Pin")
      (fields (field (name "PUBLISHER") "Altium Limited"))
      (libsource (lib "Miscellaneous Connectors") (part "Header 3"))
    )
    (comp (ref "PWR_20V")
      (value "Header 3")
      (footprint "PWR_3T")
      (description "Header, 3-Pin")
      (fields (field (name "PUBLISHER") "Altium Limited"))
      (libsource (lib "Miscellaneous Connectors") (part "Header 3"))
    )
    (comp (ref "Q1")
      (value "NUD3112")
      (footprint "SOT-23")
      (description "Relay Driver 5V Supply")
      (libsource (lib "BinFeng_IC") (part "NUD3105"))
    )
    (comp (ref "Q2")
      (value "NUD3112")
      (footprint "SOT-23")
      (description "Relay Driver 5V Supply")
      (libsource (lib "BinFeng_IC") (part "NUD3105"))
    )
    (comp (ref "Q3")
      (value "NUD3112")
      (footprint "SOT-23")
      (description "Relay Driver 5V Supply")
      (libsource (lib "BinFeng_IC") (part "NUD3105"))
    )
    (comp (ref "Q4")
      (value "NUD3112")
      (footprint "SOT-23")
      (description "Relay Driver 5V Supply")
      (libsource (lib "BinFeng_IC") (part "NUD3105"))
    )
    (comp (ref "Q9")
      (value "NUD3112")
      (footprint "SOT-23")
      (description "Relay Driver 5V Supply")
      (libsource (lib "BinFeng_IC") (part "NUD3105"))
    )
    (comp (ref "Q10")
      (value "NUD3112")
      (footprint "SOT-23")
      (description "Relay Driver 5V Supply")
      (libsource (lib "BinFeng_IC") (part "NUD3105"))
    )
    (comp (ref "Q11")
      (value "NUD3112")
      (footprint "SOT-23")
      (description "Relay Driver 5V Supply")
      (libsource (lib "BinFeng_IC") (part "NUD3105"))
    )
    (comp (ref "Q12")
      (value "NUD3112")
      (footprint "SOT-23")
      (description "Relay Driver 5V Supply")
      (libsource (lib "BinFeng_IC") (part "NUD3105"))
    )
    (comp (ref "Q13")
      (value "NUD3112")
      (footprint "SOT-23")
      (description "Relay Driver 5V Supply")
      (libsource (lib "BinFeng_IC") (part "NUD3105"))
    )
    (comp (ref "Q14")
      (value "NUD3112")
      (footprint "SOT-23")
      (description "Relay Driver 5V Supply")
      (libsource (lib "BinFeng_IC") (part "NUD3105"))
    )
    (comp (ref "Q15")
      (value "NUD3112")
      (footprint "SOT-23")
      (description "Relay Driver 5V Supply")
      (libsource (lib "BinFeng_IC") (part "NUD3105"))
    )
    (comp (ref "Q16")
      (value "NUD3112")
      (footprint "SOT-23")
      (description "Relay Driver 5V Supply")
      (libsource (lib "BinFeng_IC") (part "NUD3105"))
    )
    (comp (ref "Q17")
      (value "NUD3112")
      (footprint "SOT-23")
      (description "Relay Driver 5V Supply")
      (libsource (lib "BinFeng_IC") (part "NUD3105"))
    )
    (comp (ref "Q18")
      (value "NUD3112")
      (footprint "SOT-23")
      (description "Relay Driver 5V Supply")
      (libsource (lib "BinFeng_IC") (part "NUD3105"))
    )
    (comp (ref "Q19")
      (value "NUD3112")
      (footprint "SOT-23")
      (description "Relay Driver 5V Supply")
      (libsource (lib "BinFeng_IC") (part "NUD3105"))
    )
    (comp (ref "Q20")
      (value "NUD3112")
      (footprint "SOT-23")
      (description "Relay Driver 5V Supply")
      (libsource (lib "BinFeng_IC") (part "NUD3105"))
    )
    (comp (ref "R1")
      (value "100R")
      (footprint "BinFeng:0603")
      (description "Resistor")
      (fields (field (name "PUBLISHER") "Altium Limited"))
      (libsource (lib "Miscellaneous Devices") (part "Res1"))
    )
    (comp (ref "R2")
      (value "10K")
      (footprint "BinFeng:0603")
      (description "Resistor")
      (fields (field (name "PUBLISHER") "Altium Limited"))
      (libsource (lib "Miscellaneous Devices") (part "Res1"))
    )
    (comp (ref "R4")
      (value "100R")
      (footprint "0805")
      (description "Resistor")
      (fields (field (name "Comment") "100R_R") (field (name "PUBLISHER") "Altium Limited"))
      (libsource (lib "Miscellaneous Devices") (part "Res1"))
    )
    (comp (ref "R5")
      (value "1K")
      (footprint "0805")
      (description "Resistor")
      (fields (field (name "Comment") "1K_R") (field (name "PUBLISHER") "Altium Limited"))
      (libsource (lib "Miscellaneous Devices") (part "Res1"))
    )
    (comp (ref "R6")
      (value "10K")
      (footprint "0805")
      (description "Resistor")
      (fields (field (name "Comment") "10K_R") (field (name "PUBLISHER") "Altium Limited"))
      (libsource (lib "Miscellaneous Devices") (part "Res1"))
    )
    (comp (ref "R7")
      (value "100K")
      (footprint "0805")
      (description "Resistor")
      (fields (field (name "PUBLISHER") "Altium Limited"))
      (libsource (lib "Miscellaneous Devices") (part "Res1"))
    )
    (comp (ref "R8")
      (value "0R")
      (footprint "BinFeng:0603")
      (description "Resistor")
      (fields (field (name "PUBLISHER") "Altium Limited"))
      (libsource (lib "Miscellaneous Devices") (part "Res1"))
    )
    (comp (ref "R9")
      (value "1K")
      (footprint "BinFeng:0603")
      (description "Resistor")
      (fields (field (name "PUBLISHER") "Altium Limited"))
      (libsource (lib "Miscellaneous Devices") (part "Res1"))
    )
    (comp (ref "R13")
      (value "100R")
      (footprint "BinFeng:0603")
      (description "Resistor")
      (fields (field (name "PUBLISHER") "Altium Limited"))
      (libsource (lib "Miscellaneous Devices") (part "Res1"))
    )
    (comp (ref "R14")
      (value "5.1K")
      (footprint "0805")
      (description "Resistor")
      (fields (field (name "PUBLISHER") "Altium Limited"))
      (libsource (lib "Miscellaneous Devices") (part "Res1"))
    )
    (comp (ref "R15")
      (value "51K")
      (footprint "0805")
      (description "Resistor")
      (fields (field (name "PUBLISHER") "Altium Limited"))
      (libsource (lib "Miscellaneous Devices") (part "Res1"))
    )
    (comp (ref "R16")
      (value "5.1K")
      (footprint "0805")
      (description "Resistor")
      (fields (field (name "PUBLISHER") "Altium Limited"))
      (libsource (lib "Miscellaneous Devices") (part "Res1"))
    )
    (comp (ref "R17")
      (value "51K")
      (footprint "0805")
      (description "Resistor")
      (fields (field (name "PUBLISHER") "Altium Limited"))
      (libsource (lib "Miscellaneous Devices") (part "Res1"))
    )
    (comp (ref "R18")
      (value "5.1K")
      (footprint "0805")
      (description "Resistor")
      (fields (field (name "PUBLISHER") "Altium Limited"))
      (libsource (lib "Miscellaneous Devices") (part "Res1"))
    )
    (comp (ref "R19")
      (value "51K")
      (footprint "0805")
      (description "Resistor")
      (fields (field (name "PUBLISHER") "Altium Limited"))
      (libsource (lib "Miscellaneous Devices") (part "Res1"))
    )
    (comp (ref "R20")
      (value "51K")
      (footprint "0805")
      (description "Resistor")
      (fields (field (name "PUBLISHER") "Altium Limited"))
      (libsource (lib "Miscellaneous Devices") (part "Res1"))
    )
    (comp (ref "R21")
      (value "5.1K")
      (footprint "0805")
      (description "Resistor")
      (fields (field (name "PUBLISHER") "Altium Limited"))
      (libsource (lib "Miscellaneous Devices") (part "Res1"))
    )
    (comp (ref "R22")
      (value "5.1K")
      (footprint "0805")
      (description "Resistor")
      (fields (field (name "PUBLISHER") "Altium Limited"))
      (libsource (lib "Miscellaneous Devices") (part "Res1"))
    )
    (comp (ref "R23")
      (value "51K")
      (footprint "0805")
      (description "Resistor")
      (fields (field (name "PUBLISHER") "Altium Limited"))
      (libsource (lib "Miscellaneous Devices") (part "Res1"))
    )
    (comp (ref "R24")
      (value "5.1K")
      (footprint "0805")
      (description "Resistor")
      (fields (field (name "PUBLISHER") "Altium Limited"))
      (libsource (lib "Miscellaneous Devices") (part "Res1"))
    )
    (comp (ref "R25")
      (value "51K")
      (footprint "0805")
      (description "Resistor")
      (fields (field (name "PUBLISHER") "Altium Limited"))
      (libsource (lib "Miscellaneous Devices") (part "Res1"))
    )
    (comp (ref "R34")
      (value "5.1K")
      (footprint "0805")
      (description "Resistor")
      (fields (field (name "PUBLISHER") "Altium Limited"))
      (libsource (lib "Miscellaneous Devices") (part "Res1"))
    )
    (comp (ref "R35")
      (value "51K")
      (footprint "0805")
      (description "Resistor")
      (fields (field (name "PUBLISHER") "Altium Limited"))
      (libsource (lib "Miscellaneous Devices") (part "Res1"))
    )
    (comp (ref "R36")
      (value "5.1K")
      (footprint "0805")
      (description "Resistor")
      (fields (field (name "PUBLISHER") "Altium Limited"))
      (libsource (lib "Miscellaneous Devices") (part "Res1"))
    )
    (comp (ref "R37")
      (value "51K")
      (footprint "0805")
      (description "Resistor")
      (fields (field (name "PUBLISHER") "Altium Limited"))
      (libsource (lib "Miscellaneous Devices") (part "Res1"))
    )
    (comp (ref "R40")
      (value "22R")
      (footprint "BinFeng:0402")
      (description "Resistor")
      (fields (field (name "PUBLISHER") "Altium Limited"))
      (libsource (lib "Miscellaneous Devices") (part "Res1"))
    )
    (comp (ref "R41")
      (value "22R")
      (footprint "BinFeng:0402")
      (description "Resistor")
      (fields (field (name "PUBLISHER") "Altium Limited"))
      (libsource (lib "Miscellaneous Devices") (part "Res1"))
    )
    (comp (ref "R42")
      (value "1.5K")
      (footprint "BinFeng:0402")
      (description "Resistor")
      (fields (field (name "PUBLISHER") "Altium Limited"))
      (libsource (lib "Miscellaneous Devices") (part "Res1"))
    )
    (comp (ref "R46")
      (value "1M")
      (footprint "0805")
      (description "Resistor")
      (fields (field (name "PUBLISHER") "Altium Limited"))
      (libsource (lib "Miscellaneous Devices") (part "Res1"))
    )
    (comp (ref "R47")
      (value "10M")
      (footprint "0805")
      (description "Resistor")
      (fields (field (name "Comment") "10M_R") (field (name "PUBLISHER") "Altium Limited"))
      (libsource (lib "Miscellaneous Devices") (part "Res1"))
    )
    (comp (ref "R48")
      (value "100M")
      (footprint "0805")
      (description "Resistor")
      (fields (field (name "Comment") "100M_R") (field (name "PUBLISHER") "Altium Limited"))
      (libsource (lib "Miscellaneous Devices") (part "Res1"))
    )
    (comp (ref "R49")
      (value "1G")
      (footprint "0805")
      (description "Resistor")
      (fields (field (name "Comment") "1G_R") (field (name "PUBLISHER") "Altium Limited"))
      (libsource (lib "Miscellaneous Devices") (part "Res1"))
    )
    (comp (ref "R50")
      (value "51R")
      (footprint "0805")
      (description "Resistor")
      (fields (field (name "Comment") "51R_R") (field (name "PUBLISHER") "Altium Limited"))
      (libsource (lib "Miscellaneous Devices") (part "Res1"))
    )
    (comp (ref "R60")
      (value "9.1K")
      (footprint "BinFeng:0603")
      (description "Resistor")
      (fields (field (name "PUBLISHER") "Altium Limited"))
      (libsource (lib "Miscellaneous Devices") (part "Res1"))
    )
    (comp (ref "R61")
      (value "1K")
      (footprint "BinFeng:0603")
      (description "Resistor")
      (fields (field (name "PUBLISHER") "Altium Limited"))
      (libsource (lib "Miscellaneous Devices") (part "Res1"))
    )
    (comp (ref "R62")
      (value "1K")
      (footprint "BinFeng:0603")
      (description "Resistor")
      (fields (field (name "PUBLISHER") "Altium Limited"))
      (libsource (lib "Miscellaneous Devices") (part "Res1"))
    )
    (comp (ref "R63")
      (value "1K")
      (footprint "BinFeng:0603")
      (description "Resistor")
      (fields (field (name "PUBLISHER") "Altium Limited"))
      (libsource (lib "Miscellaneous Devices") (part "Res1"))
    )
    (comp (ref "R64")
      (value "1K")
      (footprint "BinFeng:0603")
      (description "Resistor")
      (fields (field (name "PUBLISHER") "Altium Limited"))
      (libsource (lib "Miscellaneous Devices") (part "Res1"))
    )
    (comp (ref "R65")
      (value "1K")
      (footprint "BinFeng:0603")
      (description "Resistor")
      (fields (field (name "PUBLISHER") "Altium Limited"))
      (libsource (lib "Miscellaneous Devices") (part "Res1"))
    )
    (comp (ref "R66")
      (value "2.2K")
      (footprint "BinFeng:0603")
      (description "Resistor")
      (fields (field (name "PUBLISHER") "Altium Limited"))
      (libsource (lib "Miscellaneous Devices") (part "Res1"))
    )
    (comp (ref "R67")
      (value "9.1K")
      (footprint "BinFeng:0603")
      (description "Resistor")
      (fields (field (name "PUBLISHER") "Altium Limited"))
      (libsource (lib "Miscellaneous Devices") (part "Res1"))
    )
    (comp (ref "R68")
      (value "1K")
      (footprint "BinFeng:0603")
      (description "Resistor")
      (fields (field (name "PUBLISHER") "Altium Limited"))
      (libsource (lib "Miscellaneous Devices") (part "Res1"))
    )
    (comp (ref "R69")
      (value "1K")
      (footprint "BinFeng:0603")
      (description "Resistor")
      (fields (field (name "PUBLISHER") "Altium Limited"))
      (libsource (lib "Miscellaneous Devices") (part "Res1"))
    )
    (comp (ref "R70")
      (value "1K")
      (footprint "BinFeng:0603")
      (description "Resistor")
      (fields (field (name "PUBLISHER") "Altium Limited"))
      (libsource (lib "Miscellaneous Devices") (part "Res1"))
    )
    (comp (ref "R71")
      (value "1K")
      (footprint "BinFeng:0603")
      (description "Resistor")
      (fields (field (name "PUBLISHER") "Altium Limited"))
      (libsource (lib "Miscellaneous Devices") (part "Res1"))
    )
    (comp (ref "R72")
      (value "1K")
      (footprint "BinFeng:0603")
      (description "Resistor")
      (fields (field (name "PUBLISHER") "Altium Limited"))
      (libsource (lib "Miscellaneous Devices") (part "Res1"))
    )
    (comp (ref "R73")
      (value "2.2K")
      (footprint "BinFeng:0603")
      (description "Resistor")
      (fields (field (name "PUBLISHER") "Altium Limited"))
      (libsource (lib "Miscellaneous Devices") (part "Res1"))
    )
    (comp (ref "R74")
      (value "9.1K")
      (footprint "BinFeng:0603")
      (description "Resistor")
      (fields (field (name "PUBLISHER") "Altium Limited"))
      (libsource (lib "Miscellaneous Devices") (part "Res1"))
    )
    (comp (ref "R75")
      (value "1K")
      (footprint "BinFeng:0603")
      (description "Resistor")
      (fields (field (name "PUBLISHER") "Altium Limited"))
      (libsource (lib "Miscellaneous Devices") (part "Res1"))
    )
    (comp (ref "R76")
      (value "1K")
      (footprint "BinFeng:0603")
      (description "Resistor")
      (fields (field (name "PUBLISHER") "Altium Limited"))
      (libsource (lib "Miscellaneous Devices") (part "Res1"))
    )
    (comp (ref "R77")
      (value "1K")
      (footprint "BinFeng:0603")
      (description "Resistor")
      (fields (field (name "PUBLISHER") "Altium Limited"))
      (libsource (lib "Miscellaneous Devices") (part "Res1"))
    )
    (comp (ref "R78")
      (value "1K")
      (footprint "BinFeng:0603")
      (description "Resistor")
      (fields (field (name "PUBLISHER") "Altium Limited"))
      (libsource (lib "Miscellaneous Devices") (part "Res1"))
    )
    (comp (ref "R79")
      (value "1K")
      (footprint "BinFeng:0603")
      (description "Resistor")
      (fields (field (name "PUBLISHER") "Altium Limited"))
      (libsource (lib "Miscellaneous Devices") (part "Res1"))
    )
    (comp (ref "R80")
      (value "2.2K")
      (footprint "BinFeng:0603")
      (description "Resistor")
      (fields (field (name "PUBLISHER") "Altium Limited"))
      (libsource (lib "Miscellaneous Devices") (part "Res1"))
    )
    (comp (ref "R81")
      (value "9.1K")
      (footprint "BinFeng:0603")
      (description "Resistor")
      (fields (field (name "PUBLISHER") "Altium Limited"))
      (libsource (lib "Miscellaneous Devices") (part "Res1"))
    )
    (comp (ref "R82")
      (value "1K")
      (footprint "BinFeng:0603")
      (description "Resistor")
      (fields (field (name "PUBLISHER") "Altium Limited"))
      (libsource (lib "Miscellaneous Devices") (part "Res1"))
    )
    (comp (ref "R83")
      (value "1K")
      (footprint "BinFeng:0603")
      (description "Resistor")
      (fields (field (name "PUBLISHER") "Altium Limited"))
      (libsource (lib "Miscellaneous Devices") (part "Res1"))
    )
    (comp (ref "R84")
      (value "1K")
      (footprint "BinFeng:0603")
      (description "Resistor")
      (fields (field (name "PUBLISHER") "Altium Limited"))
      (libsource (lib "Miscellaneous Devices") (part "Res1"))
    )
    (comp (ref "R85")
      (value "1K")
      (footprint "BinFeng:0603")
      (description "Resistor")
      (fields (field (name "PUBLISHER") "Altium Limited"))
      (libsource (lib "Miscellaneous Devices") (part "Res1"))
    )
    (comp (ref "R86")
      (value "1K")
      (footprint "BinFeng:0603")
      (description "Resistor")
      (fields (field (name "PUBLISHER") "Altium Limited"))
      (libsource (lib "Miscellaneous Devices") (part "Res1"))
    )
    (comp (ref "R87")
      (value "2.2K")
      (footprint "BinFeng:0603")
      (description "Resistor")
      (fields (field (name "PUBLISHER") "Altium Limited"))
      (libsource (lib "Miscellaneous Devices") (part "Res1"))
    )
    (comp (ref "R90")
      (value "0R")
      (footprint "BinFeng:0603")
      (description "Resistor")
      (fields (field (name "PUBLISHER") "Altium Limited"))
      (libsource (lib "Miscellaneous Devices") (part "Res1"))
    )
    (comp (ref "R91")
      (value "0R")
      (footprint "BinFeng:0603")
      (description "Resistor")
      (fields (field (name "Comment") "Res1") (field (name "PUBLISHER") "Altium Limited"))
      (libsource (lib "Miscellaneous Devices") (part "Res1"))
    )
    (comp (ref "R100")
      (value "120")
      (footprint "BinFeng:0603")
      (description "Resistor")
      (fields (field (name "PUBLISHER") "Altium Limited"))
      (libsource (lib "Miscellaneous Devices") (part "Res1"))
    )
    (comp (ref "R101")
      (value "NULL")
      (footprint "BinFeng:0603")
      (description "Resistor")
      (fields (field (name "PUBLISHER") "Altium Limited"))
      (libsource (lib "Miscellaneous Devices") (part "Res1"))
    )
    (comp (ref "R102")
      (value "NULL")
      (footprint "BinFeng:0603")
      (description "Resistor")
      (fields (field (name "PUBLISHER") "Altium Limited"))
      (libsource (lib "Miscellaneous Devices") (part "Res1"))
    )
    (comp (ref "R103")
      (value "120")
      (footprint "BinFeng:0603")
      (description "Resistor")
      (fields (field (name "PUBLISHER") "Altium Limited"))
      (libsource (lib "Miscellaneous Devices") (part "Res1"))
    )
    (comp (ref "R104")
      (value "NULL")
      (footprint "BinFeng:0603")
      (description "Resistor")
      (fields (field (name "PUBLISHER") "Altium Limited"))
      (libsource (lib "Miscellaneous Devices") (part "Res1"))
    )
    (comp (ref "R105")
      (value "NULL")
      (footprint "BinFeng:0603")
      (description "Resistor")
      (fields (field (name "PUBLISHER") "Altium Limited"))
      (libsource (lib "Miscellaneous Devices") (part "Res1"))
    )
    (comp (ref "RS485_2")
      (value "Header 3")
      (footprint "HDR1X3")
      (description "Header, 3-Pin")
      (fields (field (name "PUBLISHER") "Altium Limited"))
      (libsource (lib "") (part "Header 3_1"))
    )
    (comp (ref "SOURCE")
      (value "SMA")
      (footprint "SMA")
      (description "BNC Elbow Connector")
      (fields (field (name "PUBLISHER") "Altium Limited"))
      (libsource (lib "Miscellaneous Connectors") (part "BNC"))
    )
    (comp (ref "SUB")
      (value "SMA")
      (footprint "SMA")
      (description "BNC Elbow Connector")
      (fields (field (name "PUBLISHER") "Altium Limited"))
      (libsource (lib "Miscellaneous Connectors") (part "BNC"))
    )
    (comp (ref "U1")
      (value "STM32F103RET6")
      (footprint "LQFP64_N")
      (description "STM32 ARM-based 32-bit MCU with 128 Kbytes Flash, 64-pin LQFP, Industrial Temperature")
      (fields (field (name "PUBLISHER") "Altium Limited"))
      (libsource (lib "ST Microcontroller 32-Bit STM32") (part "STM32F103RBT6"))
    )
    (comp (ref "U2") (value "RT9193") (footprint "SOT-23-5") (libsource (lib "BinFeng_IC") (part "RT9193")))
    (comp (ref "U3") (value "AD5687R") (footprint "TSSOP16") (libsource (lib "BinFeng_IC") (part "AD5687R")))
    (comp (ref "U4") (value "AD5687R") (footprint "TSSOP16") (libsource (lib "BinFeng_IC") (part "AD5687R")))
    (comp (ref "U5")
      (value "ADR441")
      (footprint "SO-8N")
      (description "Ultralow Noise, XFET Voltage References")
      (libsource (lib "BinFeng_IC") (part "ADR441"))
    )
    (comp (ref "U6")
      (value "AD8601")
      (footprint "SOT-23-5")
      (description "Precision CMOS, Single Supply, Rail to Rail, Windband Operational Amplifiers")
      (libsource (lib "BinFeng_IC") (part "AD8601"))
    )
    (comp (ref "U7") (value "AD7988-1") (footprint "MSOP10") (libsource (lib "BinFeng_IC") (part "AD7988-1")))
    (comp (ref "U8") (value "AD8253") (footprint "RM-10") (libsource (lib "BinFeng_IC") (part "AD8253")))
    (comp (ref "U9")
      (value "ADR127-1.25")
      (footprint "SOT_UJ6")
      (libsource (lib "BinFeng_IC") (part "ADR127"))
    )
    (comp (ref "U19")
      (value "ADR441")
      (footprint "SO-8N")
      (description "Ultralow Noise, XFET Voltage References")
      (libsource (lib "BinFeng_IC") (part "ADR441"))
    )
    (comp (ref "U22") (value "ADA4522-2") (footprint "SO-8N") (libsource (lib "BinFeng_IC") (part "AD8676")))
    (comp (ref "U23") (value "ADA4522-2") (footprint "SO-8N") (libsource (lib "BinFeng_IC") (part "AD8676")))
    (comp (ref "U24") (value "ADA5430") (footprint "SO-8N") (libsource (lib "BinFeng_IC") (part "ADA5430")))
    (comp (ref "U26")
      (value "AD8601")
      (footprint "SOT-23-5")
      (description "Precision CMOS, Single Supply, Rail to Rail, Windband Operational Amplifiers")
      (libsource (lib "BinFeng_IC") (part "AD8601"))
    )
    (comp (ref "U29") (value "ADA4522-2") (footprint "SO-8N") (libsource (lib "BinFeng_IC") (part "AD8676")))
    (comp (ref "U30") (value "ADA4522-2") (footprint "SO-8N") (libsource (lib "BinFeng_IC") (part "AD8676")))
    (comp (ref "U32") (value "ADA4522-2") (footprint "SO-8N") (libsource (lib "BinFeng_IC") (part "AD8676")))
    (comp (ref "U33") (value "AD4522-1") (footprint "SO-8N") (libsource (lib "BinFeng_IC") (part "OP27")))
    (comp (ref "U34")
      (value "AD7791")
      (footprint "RM-10")
      (description "One channel 24 bits ADC")
      (libsource (lib "BinFeng_IC") (part "AD7791"))
    )
    (comp (ref "U35") (value "ADA4522-2") (footprint "SO-8N") (libsource (lib "BinFeng_IC") (part "AD8676")))
    (comp (ref "U36") (value "AD4522-1") (footprint "SO-8N") (libsource (lib "BinFeng_IC") (part "OP27")))
    (comp (ref "U37")
      (value "AD7791")
      (footprint "RM-10")
      (description "One channel 24 bits ADC")
      (libsource (lib "BinFeng_IC") (part "AD7791"))
    )
    (comp (ref "U38") (value "ADA4522-2") (footprint "SO-8N") (libsource (lib "BinFeng_IC") (part "AD8676")))
    (comp (ref "U39") (value "AD4522-1") (footprint "SO-8N") (libsource (lib "BinFeng_IC") (part "OP27")))
    (comp (ref "U40")
      (value "AD7791")
      (footprint "RM-10")
      (description "One channel 24 bits ADC")
      (libsource (lib "BinFeng_IC") (part "AD7791"))
    )
    (comp (ref "U41") (value "ADA4522-2") (footprint "SO-8N") (libsource (lib "BinFeng_IC") (part "AD8676")))
    (comp (ref "U42") (value "AD4522-1") (footprint "SO-8N") (libsource (lib "BinFeng_IC") (part "OP27")))
    (comp (ref "U43")
      (value "AD7791")
      (footprint "RM-10")
      (description "One channel 24 bits ADC")
      (libsource (lib "BinFeng_IC") (part "AD7791"))
    )
    (comp (ref "U44") (value "SP3485") (footprint "SO-8N") (libsource (lib "BinFeng_IC") (part "SP3485")))
    (comp (ref "U45") (value "SP3485") (footprint "SO-8N") (libsource (lib "BinFeng_IC") (part "SP3485")))
    (comp (ref "USB")
      (value "USB")
      (footprint "USB_A")
      (description "USB interface")
      (libsource (lib "BinFeng_Connectors") (part "USB_Normal"))
    )
    (comp (ref "X1") (value "8M smd") (footprint "8Mhz_XTAL") (libsource (lib "Schlib1") (part "8M smd")))
  )
  (nets
    (net (code "1") (name "+20V") (class "Default")
      (node (ref "C110") (pin "2") (pinfunction "2_2") (pintype "passive"))
      (node (ref "C111") (pin "1") (pinfunction "1_1") (pintype "passive"))
      (node (ref "C114") (pin "2") (pinfunction "2_2") (pintype "passive"))
      (node (ref "C115") (pin "1") (pinfunction "1_1") (pintype "passive"))
      (node (ref "C124") (pin "2") (pinfunction "2_2") (pintype "passive"))
      (node (ref "C129") (pin "2") (pinfunction "2_2") (pintype "passive"))
      (node (ref "C132") (pin "2") (pinfunction "2_2") (pintype "passive"))
      (node (ref "C136") (pin "2") (pinfunction "2_2") (pintype "passive"))
      (node (ref "C143") (pin "2") (pinfunction "2_2") (pintype "passive"))
      (node (ref "C147") (pin "2") (pinfunction "2_2") (pintype "passive"))
      (node (ref "C153") (pin "2") (pinfunction "2_2") (pintype "passive"))
      (node (ref "C157") (pin "2") (pinfunction "2_2") (pintype "passive"))
      (node (ref "C32") (pin "1") (pinfunction "1_1") (pintype "passive"))
      (node (ref "C33") (pin "1") (pinfunction "1_1") (pintype "passive"))
      (node (ref "C42") (pin "2") (pinfunction "2_2") (pintype "passive"))
      (node (ref "C43") (pin "1") (pinfunction "1_1") (pintype "passive"))
      (node (ref "C46") (pin "2") (pinfunction "2_2") (pintype "passive"))
      (node (ref "C47") (pin "1") (pinfunction "1_1") (pintype "passive"))
      (node (ref "C53") (pin "1") (pinfunction "1_1") (pintype "passive"))
      (node (ref "K1") (pin "2") (pintype "passive"))
      (node (ref "K10") (pin "2") (pintype "passive"))
      (node (ref "K11") (pin "2") (pintype "passive"))
      (node (ref "K12") (pin "2") (pintype "passive"))
      (node (ref "K13") (pin "2") (pintype "passive"))
      (node (ref "K14") (pin "2") (pintype "passive"))
      (node (ref "K15") (pin "2") (pintype "passive"))
      (node (ref "K16") (pin "2") (pintype "passive"))
      (node (ref "K17") (pin "2") (pintype "passive"))
      (node (ref "K18") (pin "1") (pinfunction "1_1") (pintype "passive"))
      (node (ref "K19") (pin "1") (pinfunction "1_1") (pintype "passive"))
      (node (ref "K2") (pin "2") (pintype "passive"))
      (node (ref "K20") (pin "1") (pinfunction "1_1") (pintype "passive"))
      (node (ref "K3") (pin "2") (pintype "passive"))
      (node (ref "K4") (pin "2") (pintype "passive"))
      (node (ref "K9") (pin "2") (pintype "passive"))
      (node (ref "PWR_20V") (pin "3") (pinfunction "3_3") (pintype "passive"))
      (node (ref "U22") (pin "8") (pinfunction "V+_8") (pintype "passive"))
      (node (ref "U23") (pin "8") (pinfunction "V+_8") (pintype "passive"))
      (node (ref "U29") (pin "8") (pinfunction "V+_8") (pintype "passive"))
      (node (ref "U30") (pin "8") (pinfunction "V+_8") (pintype "passive"))
      (node (ref "U32") (pin "8") (pinfunction "V+_8") (pintype "passive"))
      (node (ref "U33") (pin "7") (pinfunction "V+_7") (pintype "passive"))
      (node (ref "U35") (pin "8") (pinfunction "V+_8") (pintype "passive"))
      (node (ref "U36") (pin "7") (pinfunction "V+_7") (pintype "passive"))
      (node (ref "U38") (pin "8") (pinfunction "V+_8") (pintype "passive"))
      (node (ref "U39") (pin "7") (pinfunction "V+_7") (pintype "passive"))
      (node (ref "U41") (pin "8") (pinfunction "V+_8") (pintype "passive"))
      (node (ref "U42") (pin "7") (pinfunction "V+_7") (pintype "passive"))
    )
    (net (code "2") (name "-5V") (class "Default")
      (node (ref "C54") (pin "2") (pinfunction "2_2") (pintype "passive"))
      (node (ref "C55") (pin "2") (pinfunction "2_2") (pintype "passive"))
      (node (ref "C56") (pin "2") (pinfunction "2_2") (pintype "passive"))
      (node (ref "C79") (pin "2") (pinfunction "2_2") (pintype "passive"))
      (node (ref "C85") (pin "2") (pinfunction "2_2") (pintype "passive"))
      (node (ref "PWR_5V") (pin "1") (pinfunction "1_1") (pintype "passive"))
      (node (ref "U24") (pin "4") (pinfunction "V-_4") (pintype "passive"))
      (node (ref "U8") (pin "3") (pinfunction "-Vs_3") (pintype "passive"))
      (node (ref "U8") (pin "6") (pinfunction "/WR_6") (pintype "passive"))
    )
    (net (code "3") (name "-20V") (class "Default")
      (node (ref "C112") (pin "2") (pinfunction "2_2") (pintype "passive"))
      (node (ref "C113") (pin "2") (pinfunction "2_2") (pintype "passive"))
      (node (ref "C116") (pin "2") (pinfunction "2_2") (pintype "passive"))
      (node (ref "C117") (pin "2") (pinfunction "2_2") (pintype "passive"))
      (node (ref "C126") (pin "2") (pinfunction "2_2") (pintype "passive"))
      (node (ref "C130") (pin "2") (pinfunction "2_2") (pintype "passive"))
      (node (ref "C134") (pin "2") (pinfunction "2_2") (pintype "passive"))
      (node (ref "C137") (pin "2") (pinfunction "2_2") (pintype "passive"))
      (node (ref "C145") (pin "2") (pinfunction "2_2") (pintype "passive"))
      (node (ref "C148") (pin "2") (pinfunction "2_2") (pintype "passive"))
      (node (ref "C155") (pin "2") (pinfunction "2_2") (pintype "passive"))
      (node (ref "C160") (pin "2") (pinfunction "2_2") (pintype "passive"))
      (node (ref "C44") (pin "2") (pinfunction "2_2") (pintype "passive"))
      (node (ref "C45") (pin "2") (pinfunction "2_2") (pintype "passive"))
      (node (ref "C48") (pin "2") (pinfunction "2_2") (pintype "passive"))
      (node (ref "C49") (pin "2") (pinfunction "2_2") (pintype "passive"))
      (node (ref "C50") (pin "1") (pinfunction "1_1") (pintype "passive"))
      (node (ref "C51") (pin "2") (pinfunction "2_2") (pintype "passive"))
      (node (ref "C52") (pin "2") (pinfunction "2_2") (pintype "passive"))
      (node (ref "PWR_20V") (pin "1") (pinfunction "1_1") (pintype "passive"))
      (node (ref "U22") (pin "4") (pinfunction "V-_4") (pintype "passive"))
      (node (ref "U23") (pin "4") (pinfunction "V-_4") (pintype "passive"))
      (node (ref "U29") (pin "4") (pinfunction "V-_4") (pintype "passive"))
      (node (ref "U30") (pin "4") (pinfunction "V-_4") (pintype "passive"))
      (node (ref "U32") (pin "4") (pinfunction "V-_4") (pintype "passive"))
      (node (ref "U33") (pin "4") (pinfunction "V-_4") (pintype "passive"))
      (node (ref "U35") (pin "4") (pinfunction "V-_4") (pintype "passive"))
      (node (ref "U36") (pin "4") (pinfunction "V-_4") (pintype "passive"))
      (node (ref "U38") (pin "4") (pinfunction "V-_4") (pintype "passive"))
      (node (ref "U39") (pin "4") (pinfunction "V-_4") (pintype "passive"))
      (node (ref "U41") (pin "4") (pinfunction "V-_4") (pintype "passive"))
      (node (ref "U42") (pin "4") (pinfunction "V-_4") (pintype "passive"))
    )
    (net (code "4") (name "/1.25V") (class "Default")
      (node (ref "C89") (pin "2") (pinfunction "2_2") (pintype "passive"))
      (node (ref "U8") (pin "9") (pinfunction "REF_9") (pintype "passive"))
      (node (ref "U9") (pin "4") (pinfunction "Vout_4") (pintype "passive"))
    )
    (net (code "5") (name "/2.5V_2") (class "Default")
      (node (ref "C122") (pin "2") (pinfunction "2_2") (pintype "passive"))
      (node (ref "C139") (pin "2") (pinfunction "2_2") (pintype "passive"))
      (node (ref "C150") (pin "2") (pinfunction "2_2") (pintype "passive"))
      (node (ref "C162") (pin "2") (pinfunction "2_2") (pintype "passive"))
      (node (ref "C90") (pin "1") (pinfunction "1_1") (pintype "passive"))
      (node (ref "R63") (pin "1") (pinfunction "1_1") (pintype "passive"))
      (node (ref "R70") (pin "1") (pinfunction "1_1") (pintype "passive"))
      (node (ref "R77") (pin "1") (pinfunction "1_1") (pintype "passive"))
      (node (ref "R84") (pin "1") (pinfunction "1_1") (pintype "passive"))
      (node (ref "U34") (pin "4") (pinfunction "AIN-_4") (pintype "passive"))
      (node (ref "U34") (pin "5") (pinfunction "REF+_5") (pintype "passive"))
      (node (ref "U37") (pin "4") (pinfunction "AIN-_4") (pintype "passive"))
      (node (ref "U37") (pin "5") (pinfunction "REF+_5") (pintype "passive"))
      (node (ref "U40") (pin "4") (pinfunction "AIN-_4") (pintype "passive"))
      (node (ref "U40") (pin "5") (pinfunction "REF+_5") (pintype "passive"))
      (node (ref "U43") (pin "4") (pinfunction "AIN-_4") (pintype "passive"))
      (node (ref "U43") (pin "5") (pinfunction "REF+_5") (pintype "passive"))
      (node (ref "U6") (pin "1") (pinfunction "OUT_A_1") (pintype "passive"))
      (node (ref "U6") (pin "4") (pinfunction "-IN_4") (pintype "passive"))
      (node (ref "U7") (pin "1") (pinfunction "REF_1") (pintype "passive"))
      (node (ref "U7") (pin "2") (pinfunction "VDD_2") (pintype "passive"))
    )
    (net (code "6") (name "/2.5V_BUF1") (class "Default")
      (node (ref "C118") (pin "2") (pinfunction "2_2") (pintype "passive"))
      (node (ref "R16") (pin "1") (pinfunction "1_1") (pintype "passive"))
      (node (ref "R22") (pin "1") (pinfunction "1_1") (pintype "passive"))
      (node (ref "R34") (pin "1") (pinfunction "1_1") (pintype "passive"))
      (node (ref "R36") (pin "1") (pinfunction "1_1") (pintype "passive"))
      (node (ref "U26") (pin "1") (pinfunction "OUT_A_1") (pintype "passive"))
      (node (ref "U26") (pin "4") (pinfunction "-IN_4") (pintype "passive"))
    )
    (net (code "7") (name "/ADC_CNV") (class "Default")
      (node (ref "U1") (pin "38") (pinfunction "PC7_38") (pintype "bidirectional"))
      (node (ref "U7") (pin "6") (pinfunction "CNV_6") (pintype "passive"))
    )
    (net (code "8") (name "/ADC_SCK") (class "Default")
      (node (ref "U1") (pin "36") (pinfunction "PB15_36") (pintype "bidirectional"))
      (node (ref "U7") (pin "8") (pinfunction "SCK_8") (pintype "passive"))
    )
    (net (code "9") (name "/ADC_SDI") (class "Default")
      (node (ref "U1") (pin "35") (pinfunction "PB14_35") (pintype "bidirectional"))
      (node (ref "U7") (pin "9") (pinfunction "SDI_9") (pintype "passive"))
    )
    (net (code "10") (name "/ADC_SDO") (class "Default")
      (node (ref "U1") (pin "37") (pinfunction "PC6_37") (pintype "bidirectional"))
      (node (ref "U7") (pin "7") (pinfunction "SDO_7") (pintype "passive"))
    )
    (net (code "11") (name "/Ctrl1") (class "Default")
      (node (ref "Q1") (pin "1") (pinfunction "Gate_1") (pintype "passive"))
      (node (ref "U1") (pin "20") (pinfunction "PA4_20") (pintype "bidirectional"))
    )
    (net (code "12") (name "/Ctrl2") (class "Default")
      (node (ref "Q2") (pin "1") (pinfunction "Gate_1") (pintype "passive"))
      (node (ref "U1") (pin "21") (pinfunction "PA5_21") (pintype "bidirectional"))
    )
    (net (code "13") (name "/Ctrl3") (class "Default")
      (node (ref "Q3") (pin "1") (pinfunction "Gate_1") (pintype "passive"))
      (node (ref "U1") (pin "22") (pinfunction "PA6_22") (pintype "bidirectional"))
    )
    (net (code "14") (name "/Ctrl4") (class "Default")
      (node (ref "Q4") (pin "1") (pinfunction "Gate_1") (pintype "passive"))
      (node (ref "U1") (pin "23") (pinfunction "PA7_23") (pintype "bidirectional"))
    )
    (net (code "15") (name "/Ctrl9") (class "Default")
      (node (ref "Q9") (pin "1") (pinfunction "Gate_1") (pintype "passive"))
      (node (ref "U1") (pin "28") (pinfunction "PB2/BOOT1_28") (pintype "bidirectional"))
    )
    (net (code "16") (name "/Ctrl10") (class "Default")
      (node (ref "Q10") (pin "1") (pinfunction "Gate_1") (pintype "passive"))
      (node (ref "U1") (pin "55") (pinfunction "PB3/JTDO_55") (pintype "bidirectional"))
    )
    (net (code "17") (name "/Ctrl11") (class "Default")
      (node (ref "Q11") (pin "1") (pinfunction "Gate_1") (pintype "passive"))
      (node (ref "U1") (pin "56") (pinfunction "PB4/JNTRST_56") (pintype "bidirectional"))
    )
    (net (code "18") (name "/Ctrl12") (class "Default")
      (node (ref "Q12") (pin "1") (pinfunction "Gate_1") (pintype "passive"))
      (node (ref "U1") (pin "33") (pinfunction "PB12_33") (pintype "bidirectional"))
    )
    (net (code "19") (name "/Ctrl13") (class "Default")
      (node (ref "Q13") (pin "1") (pinfunction "Gate_1") (pintype "passive"))
      (node (ref "U1") (pin "34") (pinfunction "PB13_34") (pintype "bidirectional"))
    )
    (net (code "20") (name "/Ctrl14") (class "Default")
      (node (ref "Q14") (pin "1") (pinfunction "Gate_1") (pintype "passive"))
      (node (ref "U1") (pin "59") (pinfunction "PB7_59") (pintype "bidirectional"))
    )
    (net (code "21") (name "/Ctrl15") (class "Default")
      (node (ref "Q15") (pin "1") (pinfunction "Gate_1") (pintype "passive"))
      (node (ref "U1") (pin "4") (pinfunction "PC15-OSC32_OUT_4") (pintype "bidirectional"))
    )
    (net (code "22") (name "/Ctrl16") (class "Default")
      (node (ref "Q16") (pin "1") (pinfunction "Gate_1") (pintype "passive"))
      (node (ref "U1") (pin "2") (pinfunction "PC13-TAMPER-RTC_2") (pintype "bidirectional"))
    )
    (net (code "23") (name "/Ctrl17") (class "Default")
      (node (ref "Q17") (pin "1") (pinfunction "Gate_1") (pintype "passive"))
      (node (ref "U1") (pin "3") (pinfunction "PC14-OSC32_IN_3") (pintype "bidirectional"))
    )
    (net (code "24") (name "/Ctrl18") (class "Default")
      (node (ref "Q18") (pin "1") (pinfunction "Gate_1") (pintype "passive"))
      (node (ref "U1") (pin "57") (pinfunction "PB5_57") (pintype "bidirectional"))
    )
    (net (code "25") (name "/Ctrl19") (class "Default")
      (node (ref "Q19") (pin "1") (pinfunction "Gate_1") (pintype "passive"))
      (node (ref "U1") (pin "54") (pinfunction "PD2_54") (pintype "bidirectional"))
    )
    (net (code "26") (name "/Ctrl20") (class "Default")
      (node (ref "Q20") (pin "1") (pinfunction "Gate_1") (pintype "passive"))
      (node (ref "U1") (pin "27") (pinfunction "PB1_27") (pintype "bidirectional"))
    )
    (net (code "27") (name "/D1") (class "Default")
      (node (ref "K1") (pin "5") (pintype "passive"))
      (node (ref "Q1") (pin "3") (pinfunction "Drain_3") (pintype "passive"))
    )
    (net (code "28") (name "/D2") (class "Default")
      (node (ref "K2") (pin "5") (pintype "passive"))
      (node (ref "Q2") (pin "3") (pinfunction "Drain_3") (pintype "passive"))
    )
    (net (code "29") (name "/D3") (class "Default")
      (node (ref "K3") (pin "5") (pintype "passive"))
      (node (ref "Q3") (pin "3") (pinfunction "Drain_3") (pintype "passive"))
    )
    (net (code "30") (name "/D4") (class "Default")
      (node (ref "K4") (pin "5") (pintype "passive"))
      (node (ref "Q4") (pin "3") (pinfunction "Drain_3") (pintype "passive"))
    )
    (net (code "31") (name "/D9") (class "Default")
      (node (ref "K9") (pin "5") (pintype "passive"))
      (node (ref "Q9") (pin "3") (pinfunction "Drain_3") (pintype "passive"))
    )
    (net (code "32") (name "/D10") (class "Default")
      (node (ref "K10") (pin "5") (pintype "passive"))
      (node (ref "Q10") (pin "3") (pinfunction "Drain_3") (pintype "passive"))
    )
    (net (code "33") (name "/D11") (class "Default")
      (node (ref "K11") (pin "5") (pintype "passive"))
      (node (ref "Q11") (pin "3") (pinfunction "Drain_3") (pintype "passive"))
    )
    (net (code "34") (name "/D12") (class "Default")
      (node (ref "K12") (pin "5") (pintype "passive"))
      (node (ref "Q12") (pin "3") (pinfunction "Drain_3") (pintype "passive"))
    )
    (net (code "35") (name "/D13") (class "Default")
      (node (ref "K13") (pin "5") (pintype "passive"))
      (node (ref "Q13") (pin "3") (pinfunction "Drain_3") (pintype "passive"))
    )
    (net (code "36") (name "/D14") (class "Default")
      (node (ref "K14") (pin "5") (pintype "passive"))
      (node (ref "Q14") (pin "3") (pinfunction "Drain_3") (pintype "passive"))
    )
    (net (code "37") (name "/D15") (class "Default")
      (node (ref "K15") (pin "5") (pintype "passive"))
      (node (ref "Q15") (pin "3") (pinfunction "Drain_3") (pintype "passive"))
    )
    (net (code "38") (name "/D16") (class "Default")
      (node (ref "K16") (pin "5") (pintype "passive"))
      (node (ref "Q16") (pin "3") (pinfunction "Drain_3") (pintype "passive"))
    )
    (net (code "39") (name "/D17") (class "Default")
      (node (ref "K17") (pin "5") (pintype "passive"))
      (node (ref "Q17") (pin "3") (pinfunction "Drain_3") (pintype "passive"))
    )
    (net (code "40") (name "/D18") (class "Default")
      (node (ref "K18") (pin "8") (pinfunction "8_8") (pintype "passive"))
      (node (ref "Q18") (pin "3") (pinfunction "Drain_3") (pintype "passive"))
    )
    (net (code "41") (name "/D19") (class "Default")
      (node (ref "K19") (pin "8") (pinfunction "8_8") (pintype "passive"))
      (node (ref "Q19") (pin "3") (pinfunction "Drain_3") (pintype "passive"))
    )
    (net (code "42") (name "/D20") (class "Default")
      (node (ref "K20") (pin "8") (pinfunction "8_8") (pintype "passive"))
      (node (ref "Q20") (pin "3") (pinfunction "Drain_3") (pintype "passive"))
    )
    (net (code "43") (name "/DAC1_FSYNC") (class "Default")
      (node (ref "U1") (pin "41") (pinfunction "PA8_41") (pintype "bidirectional"))
      (node (ref "U3") (pin "13") (pinfunction "/SYNC_13") (pintype "passive"))
    )
    (net (code "44") (name "/DAC1_RESET") (class "Default")
      (node (ref "U1") (pin "14") (pinfunction "PA0-WKUP_14") (pintype "bidirectional"))
      (node (ref "U3") (pin "15") (pinfunction "/RESET_15") (pintype "passive"))
    )
    (net (code "45") (name "/DAC1_SCLK") (class "Default")
      (node (ref "U1") (pin "40") (pinfunction "PC9_40") (pintype "bidirectional"))
      (node (ref "U3") (pin "12") (pinfunction "SCLK_12") (pintype "passive"))
    )
    (net (code "46") (name "/DAC1_SDATA") (class "Default")
      (node (ref "U1") (pin "15") (pinfunction "PA1_15") (pintype "bidirectional"))
      (node (ref "U3") (pin "14") (pinfunction "SDIN_14") (pintype "passive"))
    )
    (net (code "47") (name "/DAC2_FSYNC") (class "Default")
      (node (ref "U1") (pin "10") (pinfunction "PC2_10") (pintype "bidirectional"))
      (node (ref "U4") (pin "13") (pinfunction "/SYNC_13") (pintype "passive"))
    )
    (net (code "48") (name "/DAC2_RESET") (class "Default")
      (node (ref "U1") (pin "8") (pinfunction "PC0_8") (pintype "bidirectional"))
      (node (ref "U4") (pin "15") (pinfunction "/RESET_15") (pintype "passive"))
    )
    (net (code "49") (name "/DAC2_SCLK") (class "Default")
      (node (ref "U1") (pin "11") (pinfunction "PC3_11") (pintype "bidirectional"))
      (node (ref "U4") (pin "12") (pinfunction "SCLK_12") (pintype "passive"))
    )
    (net (code "50") (name "/DAC2_SDATA") (class "Default")
      (node (ref "U1") (pin "9") (pinfunction "PC1_9") (pintype "bidirectional"))
      (node (ref "U4") (pin "14") (pinfunction "SDIN_14") (pintype "passive"))
    )
    (net (code "51") (name "/DRAIN_GUARD") (class "Default")
      (node (ref "K20") (pin "4") (pinfunction "4_4") (pintype "passive"))
      (node (ref "U30") (pin "6") (pinfunction "-IN_B_6") (pintype "passive"))
      (node (ref "U30") (pin "7") (pinfunction "Out_B_7") (pintype "passive"))
    )
    (net (code "52") (name "/DRAIN_OUT") (class "Default")
      (node (ref "C74") (pin "1") (pinfunction "1_1") (pintype "passive"))
      (node (ref "R24") (pin "1") (pinfunction "1_1") (pintype "passive"))
      (node (ref "U4") (pin "3") (pinfunction "VoutA_3") (pintype "passive"))
    )
    (net (code "53") (name "/DRAIN_SIGNAL") (class "Default")
      (node (ref "C38") (pin "2") (pinfunction "2_2") (pintype "passive"))
      (node (ref "K20") (pin "5") (pinfunction "5_5") (pintype "passive"))
      (node (ref "R25") (pin "2") (pinfunction "2_2") (pintype "passive"))
      (node (ref "U30") (pin "1") (pinfunction "Out_A_1") (pintype "passive"))
      (node (ref "U30") (pin "5") (pinfunction "+IN_B_5") (pintype "passive"))
      (node (ref "U38") (pin "3") (pinfunction "+IN_A_3") (pintype "input"))
    )
    (net (code "54") (name "/GATE_GUARD") (class "Default")
      (node (ref "K18") (pin "4") (pinfunction "4_4") (pintype "passive"))
      (node (ref "U22") (pin "6") (pinfunction "-IN_B_6") (pintype "passive"))
      (node (ref "U22") (pin "7") (pinfunction "Out_B_7") (pintype "passive"))
    )
    (net (code "55") (name "/GATE_OUT") (class "Default")
      (node (ref "C71") (pin "1") (pinfunction "1_1") (pintype "passive"))
      (node (ref "R14") (pin "1") (pinfunction "1_1") (pintype "passive"))
      (node (ref "U3") (pin "3") (pinfunction "VoutA_3") (pintype "passive"))
    )
    (net (code "56") (name "/GATE_SIGNAL") (class "Default")
      (node (ref "C40") (pin "2") (pinfunction "2_2") (pintype "passive"))
      (node (ref "K18") (pin "5") (pinfunction "5_5") (pintype "passive"))
      (node (ref "R15") (pin "2") (pinfunction "2_2") (pintype "passive"))
      (node (ref "U22") (pin "1") (pinfunction "Out_A_1") (pintype "passive"))
      (node (ref "U22") (pin "5") (pinfunction "+IN_B_5") (pintype "passive"))
      (node (ref "U32") (pin "3") (pinfunction "+IN_A_3") (pintype "input"))
    )
    (net (code "57") (name "/LED0") (class "Default")
      (node (ref "LED0") (pin "1") (pinfunction "1_1") (pintype "passive"))
      (node (ref "U1") (pin "61") (pinfunction "PB8_61") (pintype "bidirectional"))
    )
    (net (code "58") (name "/LED1") (class "Default")
      (node (ref "LED1") (pin "1") (pinfunction "1_1") (pintype "passive"))
      (node (ref "U1") (pin "62") (pinfunction "PB9_62") (pintype "bidirectional"))
    )
    (net (code "59") (name "/M_ADC_CS1") (class "Default")
      (node (ref "U1") (pin "53") (pinfunction "PC12_53") (pintype "bidirectional"))
      (node (ref "U34") (pin "2") (pinfunction "/CS_2") (pintype "passive"))
    )
    (net (code "60") (name "/M_ADC_CS2") (class "Default")
      (node (ref "U1") (pin "50") (pinfunction "PA15/JTDI_50") (pintype "bidirectional"))
      (node (ref "U37") (pin "2") (pinfunction "/CS_2") (pintype "passive"))
    )
    (net (code "61") (name "/M_ADC_CS3") (class "Default")
      (node (ref "U1") (pin "52") (pinfunction "PC11_52") (pintype "bidirectional"))
      (node (ref "U40") (pin "2") (pinfunction "/CS_2") (pintype "passive"))
    )
    (net (code "62") (name "/M_ADC_CS4") (class "Default")
      (node (ref "U1") (pin "51") (pinfunction "PC10_51") (pintype "bidirectional"))
      (node (ref "U43") (pin "2") (pinfunction "/CS_2") (pintype "passive"))
    )
    (net (code "63") (name "/M_ADC_DIN") (class "Default")
      (node (ref "U1") (pin "26") (pinfunction "PB0_26") (pintype "bidirectional"))
      (node (ref "U34") (pin "10") (pinfunction "DIN_10") (pintype "passive"))
      (node (ref "U37") (pin "10") (pinfunction "DIN_10") (pintype "passive"))
      (node (ref "U40") (pin "10") (pinfunction "DIN_10") (pintype "passive"))
      (node (ref "U43") (pin "10") (pinfunction "DIN_10") (pintype "passive"))
    )
    (net (code "64") (name "/M_ADC_DOUT") (class "Default")
      (node (ref "U1") (pin "25") (pinfunction "PC5_25") (pintype "bidirectional"))
      (node (ref "U34") (pin "9") (pinfunction "DOUT/RDY_9") (pintype "passive"))
      (node (ref "U37") (pin "9") (pinfunction "DOUT/RDY_9") (pintype "passive"))
      (node (ref "U40") (pin "9") (pinfunction "DOUT/RDY_9") (pintype "passive"))
      (node (ref "U43") (pin "9") (pinfunction "DOUT/RDY_9") (pintype "passive"))
    )
    (net (code "65") (name "/M_ADC_SCLK") (class "Default")
      (node (ref "U1") (pin "24") (pinfunction "PC4_24") (pintype "bidirectional"))
      (node (ref "U34") (pin "1") (pinfunction "SCLK_1") (pintype "passive"))
      (node (ref "U37") (pin "1") (pinfunction "SCLK_1") (pintype "passive"))
      (node (ref "U40") (pin "1") (pinfunction "SCLK_1") (pintype "passive"))
      (node (ref "U43") (pin "1") (pinfunction "SCLK_1") (pintype "passive"))
    )
    (net (code "66") (name "/PGA_OUT") (class "Default")
      (node (ref "R13") (pin "1") (pinfunction "1_1") (pintype "passive"))
      (node (ref "U8") (pin "7") (pinfunction "OUT_7") (pintype "passive"))
    )
    (net (code "67") (name "/RS485_RE") (class "Default")
      (node (ref "U1") (pin "58") (pinfunction "PB6_58") (pintype "bidirectional"))
      (node (ref "U44") (pin "2") (pinfunction "/RE_2") (pintype "passive"))
      (node (ref "U44") (pin "3") (pinfunction "DE_3") (pintype "passive"))
    )
    (net (code "68") (name "/RS485_RE2") (class "Default")
      (node (ref "U1") (pin "39") (pinfunction "PC8_39") (pintype "bidirectional"))
      (node (ref "U45") (pin "2") (pinfunction "/RE_2") (pintype "passive"))
      (node (ref "U45") (pin "3") (pinfunction "DE_3") (pintype "passive"))
    )
    (net (code "69") (name "/SOURCE_DRIVE") (class "Default")
      (node (ref "C41") (pin "1") (pinfunction "1_1") (pintype "passive"))
      (node (ref "R19") (pin "2") (pinfunction "2_2") (pintype "passive"))
      (node (ref "R91") (pin "2") (pinfunction "2_2") (pintype "passive"))
      (node (ref "U29") (pin "1") (pinfunction "Out_A_1") (pintype "passive"))
      (node (ref "U29") (pin "5") (pinfunction "+IN_B_5") (pintype "passive"))
      (node (ref "U35") (pin "3") (pinfunction "+IN_A_3") (pintype "input"))
    )
    (net (code "70") (name "/SOURCE_OUT") (class "Default")
      (node (ref "C72") (pin "1") (pinfunction "1_1") (pintype "passive"))
      (node (ref "R18") (pin "1") (pinfunction "1_1") (pintype "passive"))
      (node (ref "U3") (pin "7") (pinfunction "VoutB_7") (pintype "passive"))
    )
    (net (code "71") (name "/STAGE1_OUT") (class "Default")
      (node (ref "K1") (pin "6") (pintype "passive"))
      (node (ref "K10") (pin "6") (pintype "passive"))
      (node (ref "K11") (pin "6") (pintype "passive"))
      (node (ref "K12") (pin "6") (pintype "passive"))
      (node (ref "K13") (pin "6") (pintype "passive"))
      (node (ref "K2") (pin "6") (pintype "passive"))
      (node (ref "K3") (pin "6") (pintype "passive"))
      (node (ref "K4") (pin "6") (pintype "passive"))
      (node (ref "K9") (pin "6") (pintype "passive"))
      (node (ref "R8") (pin "2") (pinfunction "2_2") (pintype "passive"))
      (node (ref "R9") (pin "1") (pinfunction "1_1") (pintype "passive"))
      (node (ref "U8") (pin "1") (pinfunction "-IN_1") (pintype "passive"))
    )
    (net (code "72") (name "/SUB_GUARD") (class "Default")
      (node (ref "K19") (pin "4") (pinfunction "4_4") (pintype "passive"))
      (node (ref "U23") (pin "6") (pinfunction "-IN_B_6") (pintype "passive"))
      (node (ref "U23") (pin "7") (pinfunction "Out_B_7") (pintype "passive"))
    )
    (net (code "73") (name "/SUB_OUT") (class "Default")
      (node (ref "C75") (pin "1") (pinfunction "1_1") (pintype "passive"))
      (node (ref "R21") (pin "1") (pinfunction "1_1") (pintype "passive"))
      (node (ref "U4") (pin "7") (pinfunction "VoutB_7") (pintype "passive"))
    )
    (net (code "74") (name "/SUB_SIGNAL") (class "Default")
      (node (ref "C39") (pin "2") (pinfunction "2_2") (pintype "passive"))
      (node (ref "K19") (pin "5") (pinfunction "5_5") (pintype "passive"))
      (node (ref "R20") (pin "2") (pinfunction "2_2") (pintype "passive"))
      (node (ref "U23") (pin "1") (pinfunction "Out_A_1") (pintype "passive"))
      (node (ref "U23") (pin "5") (pinfunction "+IN_B_5") (pintype "passive"))
      (node (ref "U41") (pin "3") (pinfunction "+IN_A_3") (pintype "input"))
    )
    (net (code "75") (name "/SWCLK") (class "Default")
      (node (ref "DL") (pin "2") (pinfunction "D-_2") (pintype "passive"))
      (node (ref "U1") (pin "49") (pinfunction "PA14/JTCK/SWCLK_49") (pintype "bidirectional"))
    )
    (net (code "76") (name "/SWDIO") (class "Default")
      (node (ref "DL") (pin "3") (pinfunction "D+_3") (pintype "passive"))
      (node (ref "DL") (pin "4") (pinfunction "ID_4") (pintype "passive"))
      (node (ref "U1") (pin "46") (pinfunction "PA13/JTMS/SWDIO_46") (pintype "bidirectional"))
    )
    (net (code "77") (name "/UART3_RX") (class "Default")
      (node (ref "LCD") (pin "5") (pinfunction "5_5") (pintype "passive"))
      (node (ref "U1") (pin "30") (pinfunction "PB11_30") (pintype "bidirectional"))
    )
    (net (code "78") (name "/UART3_TX") (class "Default")
      (node (ref "LCD") (pin "3") (pinfunction "3_3") (pintype "passive"))
      (node (ref "LCD") (pin "4") (pinfunction "4_4") (pintype "passive"))
      (node (ref "U1") (pin "29") (pinfunction "PB10_29") (pintype "bidirectional"))
    )
    (net (code "79") (name "/USART1_RX") (class "Default")
      (node (ref "U1") (pin "43") (pinfunction "PA10_43") (pintype "bidirectional"))
      (node (ref "U44") (pin "1") (pinfunction "RO_1") (pintype "passive"))
    )
    (net (code "80") (name "/USART1_TX") (class "Default")
      (node (ref "U1") (pin "42") (pinfunction "PA9_42") (pintype "bidirectional"))
      (node (ref "U44") (pin "4") (pinfunction "DI_4") (pintype "passive"))
    )
    (net (code "81") (name "/USART2_RX") (class "Default")
      (node (ref "U1") (pin "17") (pinfunction "PA3_17") (pintype "bidirectional"))
      (node (ref "U45") (pin "1") (pinfunction "RO_1") (pintype "passive"))
    )
    (net (code "82") (name "/USART2_TX") (class "Default")
      (node (ref "U1") (pin "16") (pinfunction "PA2_16") (pintype "bidirectional"))
      (node (ref "U45") (pin "4") (pinfunction "DI_4") (pintype "passive"))
    )
    (net (code "83") (name "/USB_DM") (class "Default")
      (node (ref "R40") (pin "2") (pinfunction "2_2") (pintype "passive"))
      (node (ref "U1") (pin "44") (pinfunction "PA11_44") (pintype "bidirectional"))
    )
    (net (code "84") (name "/USB_DP") (class "Default")
      (node (ref "R41") (pin "2") (pinfunction "2_2") (pintype "passive"))
      (node (ref "R42") (pin "2") (pinfunction "2_2") (pintype "passive"))
      (node (ref "U1") (pin "45") (pinfunction "PA12_45") (pintype "bidirectional"))
    )
    (net (code "85") (name "5V") (class "Default")
      (node (ref "C120") (pin "2") (pinfunction "2_2") (pintype "passive"))
      (node (ref "C140") (pin "2") (pinfunction "2_2") (pintype "passive"))
      (node (ref "C151") (pin "2") (pinfunction "2_2") (pintype "passive"))
      (node (ref "C163") (pin "2") (pinfunction "2_2") (pintype "passive"))
      (node (ref "C30") (pin "2") (pinfunction "2_2") (pintype "passive"))
      (node (ref "C31") (pin "2") (pinfunction "2_2") (pintype "passive"))
      (node (ref "C34") (pin "2") (pinfunction "2_2") (pintype "passive"))
      (node (ref "C35") (pin "1") (pinfunction "1_1") (pintype "passive"))
      (node (ref "C36") (pin "2") (pinfunction "2_2") (pintype "passive"))
      (node (ref "C37") (pin "1") (pinfunction "1_1") (pintype "passive"))
      (node (ref "C60") (pin "1") (pinfunction "1_1") (pintype "passive"))
      (node (ref "C61") (pin "1") (pinfunction "1_1") (pintype "passive"))
      (node (ref "C62") (pin "2") (pinfunction "2_2") (pintype "passive"))
      (node (ref "C78") (pin "2") (pinfunction "2_2") (pintype "passive"))
      (node (ref "C82") (pin "2") (pinfunction "2_2") (pintype "passive"))
      (node (ref "C83") (pin "2") (pinfunction "2_2") (pintype "passive"))
      (node (ref "C84") (pin "2") (pinfunction "2_2") (pintype "passive"))
      (node (ref "C86") (pin "2") (pinfunction "2_2") (pintype "passive"))
      (node (ref "L2") (pin "1") (pinfunction "1_1") (pintype "passive"))
      (node (ref "PWR_5V") (pin "3") (pinfunction "3_3") (pintype "passive"))
      (node (ref "U19") (pin "2") (pinfunction "Vin_2") (pintype "passive"))
      (node (ref "U24") (pin "5") (pinfunction "V+_5") (pintype "passive"))
      (node (ref "U26") (pin "5") (pinfunction "V+_5") (pintype "passive"))
      (node (ref "U3") (pin "5") (pinfunction "Vdd_5") (pintype "passive"))
      (node (ref "U34") (pin "8") (pinfunction "Vdd_8") (pintype "passive"))
      (node (ref "U37") (pin "8") (pinfunction "Vdd_8") (pintype "passive"))
      (node (ref "U4") (pin "5") (pinfunction "Vdd_5") (pintype "passive"))
      (node (ref "U40") (pin "8") (pinfunction "Vdd_8") (pintype "passive"))
      (node (ref "U43") (pin "8") (pinfunction "Vdd_8") (pintype "passive"))
      (node (ref "U5") (pin "2") (pinfunction "Vin_2") (pintype "passive"))
      (node (ref "U6") (pin "5") (pinfunction "V+_5") (pintype "passive"))
      (node (ref "U8") (pin "8") (pinfunction "+Vs_8") (pintype "passive"))
      (node (ref "U9") (pin "3") (pinfunction "Vin_3") (pintype "passive"))
    )
    (net (code "86") (name "AGND") (class "Default")
      (node (ref "C110") (pin "1") (pinfunction "1_1") (pintype "passive"))
      (node (ref "C111") (pin "2") (pinfunction "2_2") (pintype "passive"))
      (node (ref "C112") (pin "1") (pinfunction "1_1") (pintype "passive"))
      (node (ref "C113") (pin "1") (pinfunction "1_1") (pintype "passive"))
      (node (ref "C114") (pin "1") (pinfunction "1_1") (pintype "passive"))
      (node (ref "C115") (pin "2") (pinfunction "2_2") (pintype "passive"))
      (node (ref "C116") (pin "1") (pinfunction "1_1") (pintype "passive"))
      (node (ref "C117") (pin "1") (pinfunction "1_1") (pintype "passive"))
      (node (ref "C118") (pin "1") (pinfunction "1_1") (pintype "passive"))
      (node (ref "C120") (pin "1") (pinfunction "1_1") (pintype "passive"))
      (node (ref "C122") (pin "1") (pinfunction "1_1") (pintype "passive"))
      (node (ref "C124") (pin "1") (pinfunction "1_1") (pintype "passive"))
      (node (ref "C126") (pin "1") (pinfunction "1_1") (pintype "passive"))
      (node (ref "C129") (pin "1") (pinfunction "1_1") (pintype "passive"))
      (node (ref "C130") (pin "1") (pinfunction "1_1") (pintype "passive"))
      (node (ref "C131") (pin "1") (pinfunction "1_1") (pintype "passive"))
      (node (ref "C132") (pin "1") (pinfunction "1_1") (pintype "passive"))
      (node (ref "C134") (pin "1") (pinfunction "1_1") (pintype "passive"))
      (node (ref "C136") (pin "1") (pinfunction "1_1") (pintype "passive"))
      (node (ref "C137") (pin "1") (pinfunction "1_1") (pintype "passive"))
      (node (ref "C138") (pin "1") (pinfunction "1_1") (pintype "passive"))
      (node (ref "C139") (pin "1") (pinfunction "1_1") (pintype "passive"))
      (node (ref "C140") (pin "1") (pinfunction "1_1") (pintype "passive"))
      (node (ref "C143") (pin "1") (pinfunction "1_1") (pintype "passive"))
      (node (ref "C145") (pin "1") (pinfunction "1_1") (pintype "passive"))
      (node (ref "C147") (pin "1") (pinfunction "1_1") (pintype "passive"))
      (node (ref "C148") (pin "1") (pinfunction "1_1") (pintype "passive"))
      (node (ref "C149") (pin "1") (pinfunction "1_1") (pintype "passive"))
      (node (ref "C150") (pin "1") (pinfunction "1_1") (pintype "passive"))
      (node (ref "C151") (pin "1") (pinfunction "1_1") (pintype "passive"))
      (node (ref "C153") (pin "1") (pinfunction "1_1") (pintype "passive"))
      (node (ref "C155") (pin "1") (pinfunction "1_1") (pintype "passive"))
      (node (ref "C157") (pin "1") (pinfunction "1_1") (pintype "passive"))
      (node (ref "C160") (pin "1") (pinfunction "1_1") (pintype "passive"))
      (node (ref "C161") (pin "1") (pinfunction "1_1") (pintype "passive"))
      (node (ref "C162") (pin "1") (pinfunction "1_1") (pintype "passive"))
      (node (ref "C163") (pin "1") (pinfunction "1_1") (pintype "passive"))
      (node (ref "C30") (pin "1") (pinfunction "1_1") (pintype "passive"))
      (node (ref "C31") (pin "1") (pinfunction "1_1") (pintype "passive"))
      (node (ref "C32") (pin "2") (pinfunction "2_2") (pintype "passive"))
      (node (ref "C33") (pin "2") (pinfunction "2_2") (pintype "passive"))
      (node (ref "C34") (pin "1") (pinfunction "1_1") (pintype "passive"))
      (node (ref "C35") (pin "2") (pinfunction "2_2") (pintype "passive"))
      (node (ref "C36") (pin "1") (pinfunction "1_1") (pintype "passive"))
      (node (ref "C37") (pin "2") (pinfunction "2_2") (pintype "passive"))
      (node (ref "C42") (pin "1") (pinfunction "1_1") (pintype "passive"))
      (node (ref "C43") (pin "2") (pinfunction "2_2") (pintype "passive"))
      (node (ref "C44") (pin "1") (pinfunction "1_1") (pintype "passive"))
      (node (ref "C45") (pin "1") (pinfunction "1_1") (pintype "passive"))
      (node (ref "C46") (pin "1") (pinfunction "1_1") (pintype "passive"))
      (node (ref "C47") (pin "2") (pinfunction "2_2") (pintype "passive"))
      (node (ref "C48") (pin "1") (pinfunction "1_1") (pintype "passive"))
      (node (ref "C49") (pin "1") (pinfunction "1_1") (pintype "passive"))
      (node (ref "C50") (pin "2") (pinfunction "2_2") (pintype "passive"))
      (node (ref "C51") (pin "1") (pinfunction "1_1") (pintype "passive"))
      (node (ref "C52") (pin "1") (pinfunction "1_1") (pintype "passive"))
      (node (ref "C53") (pin "2") (pinfunction "2_2") (pintype "passive"))
      (node (ref "C54") (pin "1") (pinfunction "1_1") (pintype "passive"))
      (node (ref "C55") (pin "1") (pinfunction "1_1") (pintype "passive"))
      (node (ref "C56") (pin "1") (pinfunction "1_1") (pintype "passive"))
      (node (ref "C60") (pin "2") (pinfunction "2_2") (pintype "passive"))
      (node (ref "C61") (pin "2") (pinfunction "2_2") (pintype "passive"))
      (node (ref "C62") (pin "1") (pinfunction "1_1") (pintype "passive"))
      (node (ref "C71") (pin "2") (pinfunction "2_2") (pintype "passive"))
      (node (ref "C72") (pin "2") (pinfunction "2_2") (pintype "passive"))
      (node (ref "C73") (pin "2") (pinfunction "2_2") (pintype "passive"))
      (node (ref "C74") (pin "2") (pinfunction "2_2") (pintype "passive"))
      (node (ref "C75") (pin "2") (pinfunction "2_2") (pintype "passive"))
      (node (ref "C76") (pin "2") (pinfunction "2_2") (pintype "passive"))
      (node (ref "C78") (pin "1") (pinfunction "1_1") (pintype "passive"))
      (node (ref "C79") (pin "1") (pinfunction "1_1") (pintype "passive"))
      (node (ref "C80") (pin "2") (pinfunction "2_2") (pintype "passive"))
      (node (ref "C82") (pin "1") (pinfunction "1_1") (pintype "passive"))
      (node (ref "C83") (pin "1") (pinfunction "1_1") (pintype "passive"))
      (node (ref "C84") (pin "1") (pinfunction "1_1") (pintype "passive"))
      (node (ref "C85") (pin "1") (pinfunction "1_1") (pintype "passive"))
      (node (ref "C86") (pin "1") (pinfunction "1_1") (pintype "passive"))
      (node (ref "C89") (pin "1") (pinfunction "1_1") (pintype "passive"))
      (node (ref "C90") (pin "2") (pinfunction "2_2") (pintype "passive"))
      (node (ref "C91") (pin "1") (pinfunction "1_1") (pintype "passive"))
      (node (ref "C92") (pin "1") (pinfunction "1_1") (pintype "passive"))
      (node (ref "L3") (pin "1") (pinfunction "1_1") (pintype "passive"))
      (node (ref "PWR_20V") (pin "2") (pinfunction "2_2") (pintype "passive"))
      (node (ref "PWR_5V") (pin "2") (pinfunction "2_2") (pintype "passive"))
      (node (ref "Q1") (pin "2") (pinfunction "Source_2") (pintype "passive"))
      (node (ref "Q10") (pin "2") (pinfunction "Source_2") (pintype "passive"))
      (node (ref "Q11") (pin "2") (pinfunction "Source_2") (pintype "passive"))
      (node (ref "Q12") (pin "2") (pinfunction "Source_2") (pintype "passive"))
      (node (ref "Q13") (pin "2") (pinfunction "Source_2") (pintype "passive"))
      (node (ref "Q14") (pin "2") (pinfunction "Source_2") (pintype "passive"))
      (node (ref "Q15") (pin "2") (pinfunction "Source_2") (pintype "passive"))
      (node (ref "Q16") (pin "2") (pinfunction "Source_2") (pintype "passive"))
      (node (ref "Q17") (pin "2") (pinfunction "Source_2") (pintype "passive"))
      (node (ref "Q18") (pin "2") (pinfunction "Source_2") (pintype "passive"))
      (node (ref "Q19") (pin "2") (pinfunction "Source_2") (pintype "passive"))
      (node (ref "Q2") (pin "2") (pinfunction "Source_2") (pintype "passive"))
      (node (ref "Q20") (pin "2") (pinfunction "Source_2") (pintype "passive"))
      (node (ref "Q3") (pin "2") (pinfunction "Source_2") (pintype "passive"))
      (node (ref "Q4") (pin "2") (pinfunction "Source_2") (pintype "passive"))
      (node (ref "Q9") (pin "2") (pinfunction "Source_2") (pintype "passive"))
      (node (ref "R17") (pin "1") (pinfunction "1_1") (pintype "passive"))
      (node (ref "R23") (pin "1") (pinfunction "1_1") (pintype "passive"))
      (node (ref "R35") (pin "1") (pinfunction "1_1") (pintype "passive"))
      (node (ref "R37") (pin "1") (pinfunction "1_1") (pintype "passive"))
      (node (ref "R61") (pin "2") (pinfunction "2_2") (pintype "passive"))
      (node (ref "R64") (pin "2") (pinfunction "2_2") (pintype "passive"))
      (node (ref "R68") (pin "2") (pinfunction "2_2") (pintype "passive"))
      (node (ref "R71") (pin "2") (pinfunction "2_2") (pintype "passive"))
      (node (ref "R75") (pin "2") (pinfunction "2_2") (pintype "passive"))
      (node (ref "R78") (pin "2") (pinfunction "2_2") (pintype "passive"))
      (node (ref "R82") (pin "2") (pinfunction "2_2") (pintype "passive"))
      (node (ref "R85") (pin "2") (pinfunction "2_2") (pintype "passive"))
      (node (ref "R9") (pin "2") (pinfunction "2_2") (pintype "passive"))
      (node (ref "R90") (pin "2") (pinfunction "2_2") (pintype "passive"))
      (node (ref "U19") (pin "4") (pinfunction "GND_4") (pintype "passive"))
      (node (ref "U26") (pin "2") (pinfunction "V-_2") (pintype "passive"))
      (node (ref "U3") (pin "16") (pinfunction "RSTSEL_16") (pintype "passive"))
      (node (ref "U3") (pin "4") (pinfunction "GND_4") (pintype "passive"))
      (node (ref "U3") (pin "9") (pinfunction "/LDAC_9") (pintype "passive"))
      (node (ref "U34") (pin "6") (pinfunction "REF-_6") (pintype "passive"))
      (node (ref "U34") (pin "7") (pinfunction "GND_7") (pintype "passive"))
      (node (ref "U37") (pin "6") (pinfunction "REF-_6") (pintype "passive"))
      (node (ref "U37") (pin "7") (pinfunction "GND_7") (pintype "passive"))
      (node (ref "U4") (pin "16") (pinfunction "RSTSEL_16") (pintype "passive"))
      (node (ref "U4") (pin "4") (pinfunction "GND_4") (pintype "passive"))
      (node (ref "U4") (pin "9") (pinfunction "/LDAC_9") (pintype "passive"))
      (node (ref "U40") (pin "6") (pinfunction "REF-_6") (pintype "passive"))
      (node (ref "U40") (pin "7") (pinfunction "GND_7") (pintype "passive"))
      (node (ref "U43") (pin "6") (pinfunction "REF-_6") (pintype "passive"))
      (node (ref "U43") (pin "7") (pinfunction "GND_7") (pintype "passive"))
      (node (ref "U5") (pin "4") (pinfunction "GND_4") (pintype "passive"))
      (node (ref "U6") (pin "2") (pinfunction "V-_2") (pintype "passive"))
      (node (ref "U7") (pin "4") (pinfunction "IN-_4") (pintype "passive"))
      (node (ref "U7") (pin "5") (pinfunction "GND_5") (pintype "passive"))
      (node (ref "U8") (pin "10") (pinfunction "+IN_10") (pintype "passive"))
      (node (ref "U8") (pin "2") (pinfunction "DGND_2") (pintype "passive"))
      (node (ref "U8") (pin "4") (pinfunction "A0_4") (pintype "passive"))
      (node (ref "U8") (pin "5") (pinfunction "A1_5") (pintype "passive"))
      (node (ref "U9") (pin "2") (pinfunction "GND_2") (pintype "passive"))
    )
    (net (code "87") (name "D3V3") (class "Default")
      (node (ref "C1") (pin "2") (pinfunction "2_2") (pintype "passive"))
      (node (ref "C108") (pin "2") (pinfunction "2_2") (pintype "passive"))
      (node (ref "C2") (pin "2") (pinfunction "2_2") (pintype "passive"))
      (node (ref "C22") (pin "2") (pinfunction "2_2") (pintype "passive"))
      (node (ref "C29") (pin "2") (pinfunction "2_2") (pintype "passive"))
      (node (ref "C3") (pin "2") (pinfunction "2_2") (pintype "passive"))
      (node (ref "C4") (pin "2") (pinfunction "2_2") (pintype "passive"))
      (node (ref "C5") (pin "2") (pinfunction "2_2") (pintype "passive"))
      (node (ref "C6") (pin "2") (pinfunction "2_2") (pintype "passive"))
      (node (ref "C77") (pin "2") (pinfunction "2_2") (pintype "passive"))
      (node (ref "LED0") (pin "2") (pinfunction "2_2") (pintype "passive"))
      (node (ref "LED1") (pin "2") (pinfunction "2_2") (pintype "passive"))
      (node (ref "R102") (pin "2") (pinfunction "2_2") (pintype "passive"))
      (node (ref "R105") (pin "2") (pinfunction "2_2") (pintype "passive"))
      (node (ref "R42") (pin "1") (pinfunction "1_1") (pintype "passive"))
      (node (ref "U1") (pin "1") (pinfunction "VBAT_1") (pintype "power_in"))
      (node (ref "U1") (pin "13") (pinfunction "VDDA_13") (pintype "power_in"))
      (node (ref "U1") (pin "19") (pinfunction "VDD_4_19") (pintype "power_in"))
      (node (ref "U1") (pin "32") (pinfunction "VDD_1_32") (pintype "power_in"))
      (node (ref "U1") (pin "48") (pinfunction "VDD_2_48") (pintype "power_in"))
      (node (ref "U1") (pin "64") (pinfunction "VDD_3_64") (pintype "power_in"))
      (node (ref "U2") (pin "5") (pinfunction "VOUT_5") (pintype "passive"))
      (node (ref "U3") (pin "10") (pinfunction "GAIN_10") (pintype "passive"))
      (node (ref "U3") (pin "11") (pinfunction "Vlogic_11") (pintype "passive"))
      (node (ref "U4") (pin "10") (pinfunction "GAIN_10") (pintype "passive"))
      (node (ref "U4") (pin "11") (pinfunction "Vlogic_11") (pintype "passive"))
      (node (ref "U44") (pin "8") (pinfunction "VCC_8") (pintype "passive"))
      (node (ref "U45") (pin "8") (pinfunction "VCC_8") (pintype "passive"))
      (node (ref "U7") (pin "10") (pinfunction "VIO_10") (pintype "passive"))
    )
    (net (code "88") (name "D5V0") (class "Default")
      (node (ref "C57") (pin "2") (pinfunction "2_2") (pintype "passive"))
      (node (ref "C58") (pin "2") (pinfunction "2_2") (pintype "passive"))
      (node (ref "C59") (pin "1") (pinfunction "1_1") (pintype "passive"))
      (node (ref "L2") (pin "2") (pinfunction "2_2") (pintype "passive"))
      (node (ref "LCD") (pin "7") (pinfunction "7_7") (pintype "passive"))
      (node (ref "LCD") (pin "8") (pinfunction "8_8") (pintype "passive"))
      (node (ref "U2") (pin "1") (pinfunction "VIN_1") (pintype "passive"))
      (node (ref "U2") (pin "3") (pinfunction "EN_3") (pintype "passive"))
    )
    (net (code "89") (name "DGND") (class "Default")
      (node (ref "C1") (pin "1") (pinfunction "1_1") (pintype "passive"))
      (node (ref "C108") (pin "1") (pinfunction "1_1") (pintype "passive"))
      (node (ref "C2") (pin "1") (pinfunction "1_1") (pintype "passive"))
      (node (ref "C21") (pin "1") (pinfunction "1_1") (pintype "passive"))
      (node (ref "C22") (pin "1") (pinfunction "1_1") (pintype "passive"))
      (node (ref "C29") (pin "1") (pinfunction "1_1") (pintype "passive"))
      (node (ref "C3") (pin "1") (pinfunction "1_1") (pintype "passive"))
      (node (ref "C4") (pin "1") (pinfunction "1_1") (pintype "passive"))
      (node (ref "C5") (pin "1") (pinfunction "1_1") (pintype "passive"))
      (node (ref "C57") (pin "1") (pinfunction "1_1") (pintype "passive"))
      (node (ref "C58") (pin "1") (pinfunction "1_1") (pintype "passive"))
      (node (ref "C59") (pin "2") (pinfunction "2_2") (pintype "passive"))
      (node (ref "C6") (pin "1") (pinfunction "1_1") (pintype "passive"))
      (node (ref "C77") (pin "1") (pinfunction "1_1") (pintype "passive"))
      (node (ref "DL") (pin "5") (pinfunction "VSS_5") (pintype "passive"))
      (node (ref "L1") (pin "2") (pinfunction "2_2") (pintype "passive"))
      (node (ref "L3") (pin "2") (pinfunction "2_2") (pintype "passive"))
      (node (ref "LCD") (pin "1") (pinfunction "1_1") (pintype "passive"))
      (node (ref "LCD") (pin "2") (pinfunction "2_2") (pintype "passive"))
      (node (ref "R101") (pin "2") (pinfunction "2_2") (pintype "passive"))
      (node (ref "R104") (pin "2") (pinfunction "2_2") (pintype "passive"))
      (node (ref "R2") (pin "2") (pinfunction "2_2") (pintype "passive"))
      (node (ref "RS485_2") (pin "3") (pinfunction "3_3") (pintype "passive"))
      (node (ref "U1") (pin "12") (pinfunction "VSSA_12") (pintype "power_in"))
      (node (ref "U1") (pin "18") (pinfunction "VSS_4_18") (pintype "power_in"))
      (node (ref "U1") (pin "31") (pinfunction "VSS_1_31") (pintype "power_in"))
      (node (ref "U1") (pin "47") (pinfunction "VSS_2_47") (pintype "power_in"))
      (node (ref "U1") (pin "63") (pinfunction "VSS_3_63") (pintype "power_in"))
      (node (ref "U2") (pin "2") (pinfunction "GND_2") (pintype "passive"))
      (node (ref "U44") (pin "5") (pinfunction "GND_5") (pintype "passive"))
      (node (ref "U45") (pin "5") (pinfunction "GND_5") (pintype "passive"))
      (node (ref "USB") (pin "4") (pinfunction "GND_4") (pintype "passive"))
      (node (ref "X1") (pin "2") (pinfunction "GND_2") (pintype "passive"))
    )
    (net (code "90") (name "Net-(C63-Pad1)") (class "Default")
      (node (ref "C63") (pin "1") (pinfunction "1_1") (pintype "passive"))
      (node (ref "K1") (pin "4") (pintype "passive"))
      (node (ref "R4") (pin "2") (pinfunction "2_2") (pintype "passive"))
    )
    (net (code "91") (name "Net-(C64-Pad1)") (class "Default")
      (node (ref "C64") (pin "1") (pinfunction "1_1") (pintype "passive"))
      (node (ref "K2") (pin "4") (pintype "passive"))
      (node (ref "R5") (pin "2") (pinfunction "2_2") (pintype "passive"))
    )
    (net (code "92") (name "Net-(C65-Pad1)") (class "Default")
      (node (ref "C65") (pin "1") (pinfunction "1_1") (pintype "passive"))
      (node (ref "K3") (pin "4") (pintype "passive"))
      (node (ref "R6") (pin "2") (pinfunction "2_2") (pintype "passive"))
    )
    (net (code "93") (name "Net-(C66-Pad1)") (class "Default")
      (node (ref "C66") (pin "1") (pinfunction "1_1") (pintype "passive"))
      (node (ref "K4") (pin "4") (pintype "passive"))
      (node (ref "R7") (pin "2") (pinfunction "2_2") (pintype "passive"))
    )
    (net (code "94") (name "Net-(C100-Pad1)") (class "Default")
      (node (ref "C100") (pin "1") (pinfunction "1_1") (pintype "passive"))
      (node (ref "K9") (pin "4") (pintype "passive"))
      (node (ref "R46") (pin "2") (pinfunction "2_2") (pintype "passive"))
    )
    (net (code "95") (name "Net-(C101-Pad1)") (class "Default")
      (node (ref "C101") (pin "1") (pinfunction "1_1") (pintype "passive"))
      (node (ref "K10") (pin "4") (pintype "passive"))
      (node (ref "R47") (pin "2") (pinfunction "2_2") (pintype "passive"))
    )
    (net (code "96") (name "Net-(C102-Pad1)") (class "Default")
      (node (ref "C102") (pin "1") (pinfunction "1_1") (pintype "passive"))
      (node (ref "K11") (pin "4") (pintype "passive"))
      (node (ref "R48") (pin "2") (pinfunction "2_2") (pintype "passive"))
    )
    (net (code "97") (name "Net-(C103-Pad1)") (class "Default")
      (node (ref "C103") (pin "1") (pinfunction "1_1") (pintype "passive"))
      (node (ref "K12") (pin "4") (pintype "passive"))
      (node (ref "R49") (pin "2") (pinfunction "2_2") (pintype "passive"))
    )
    (net (code "98") (name "Net-(C104-Pad1)") (class "Default")
      (node (ref "C104") (pin "1") (pinfunction "1_1") (pintype "passive"))
      (node (ref "K13") (pin "4") (pintype "passive"))
      (node (ref "R50") (pin "2") (pinfunction "2_2") (pintype "passive"))
    )
    (net (code "99") (name "Net-(DRAIN-X)") (class "Default")
      (node (ref "DRAIN") (pin "1") (pinfunction "X_1") (pintype "passive"))
      (node (ref "K20") (pin "6") (pinfunction "6_6") (pintype "passive"))
    )
    (net (code "100") (name "Net-(DRAIN-Y)") (class "Default")
      (node (ref "DRAIN") (pin "2") (pinfunction "Y_2") (pintype "passive"))
      (node (ref "K20") (pin "3") (pinfunction "3_3") (pintype "passive"))
    )
    (net (code "101") (name "Net-(GATE-X)") (class "Default")
      (node (ref "GATE") (pin "1") (pinfunction "X_1") (pintype "passive"))
      (node (ref "K18") (pin "6") (pinfunction "6_6") (pintype "passive"))
    )
    (net (code "102") (name "Net-(GATE-Y)") (class "Default")
      (node (ref "GATE") (pin "2") (pinfunction "Y_2") (pintype "passive"))
      (node (ref "K18") (pin "3") (pinfunction "3_3") (pintype "passive"))
    )
    (net (code "103") (name "Net-(L1-Pad1)") (class "Default")
      (node (ref "L1") (pin "1") (pinfunction "1_1") (pintype "passive"))
      (node (ref "USB") (pin "5") (pinfunction "VSS_5") (pintype "passive"))
      (node (ref "USB") (pin "6") (pinfunction "VSS_6") (pintype "passive"))
    )
    (net (code "104") (name "Net-(SOURCE-X)") (class "Default")
      (node (ref "C100") (pin "2") (pinfunction "2_2") (pintype "passive"))
      (node (ref "C101") (pin "2") (pinfunction "2_2") (pintype "passive"))
      (node (ref "C102") (pin "2") (pinfunction "2_2") (pintype "passive"))
      (node (ref "C103") (pin "2") (pinfunction "2_2") (pintype "passive"))
      (node (ref "C104") (pin "2") (pinfunction "2_2") (pintype "passive"))
      (node (ref "C63") (pin "2") (pinfunction "2_2") (pintype "passive"))
      (node (ref "C64") (pin "2") (pinfunction "2_2") (pintype "passive"))
      (node (ref "C65") (pin "2") (pinfunction "2_2") (pintype "passive"))
      (node (ref "C66") (pin "2") (pinfunction "2_2") (pintype "passive"))
      (node (ref "R4") (pin "1") (pinfunction "1_1") (pintype "passive"))
      (node (ref "R46") (pin "1") (pinfunction "1_1") (pintype "passive"))
      (node (ref "R47") (pin "1") (pinfunction "1_1") (pintype "passive"))
      (node (ref "R48") (pin "1") (pinfunction "1_1") (pintype "passive"))
      (node (ref "R49") (pin "1") (pinfunction "1_1") (pintype "passive"))
      (node (ref "R5") (pin "1") (pinfunction "1_1") (pintype "passive"))
      (node (ref "R50") (pin "1") (pinfunction "1_1") (pintype "passive"))
      (node (ref "R6") (pin "1") (pinfunction "1_1") (pintype "passive"))
      (node (ref "R7") (pin "1") (pinfunction "1_1") (pintype "passive"))
      (node (ref "SOURCE") (pin "1") (pinfunction "X_1") (pintype "passive"))
      (node (ref "U24") (pin "8") (pinfunction "IN-_8") (pintype "passive"))
    )
    (net (code "105") (name "Net-(SOURCE-Y)") (class "Default")
      (node (ref "SOURCE") (pin "2") (pinfunction "Y_2") (pintype "passive"))
      (node (ref "U24") (pin "2") (pinfunction "GRD_2") (pintype "passive"))
      (node (ref "U24") (pin "7") (pinfunction "GRD_7") (pintype "passive"))
    )
    (net (code "106") (name "Net-(SUB-X)") (class "Default")
      (node (ref "K19") (pin "6") (pinfunction "6_6") (pintype "passive"))
      (node (ref "SUB") (pin "1") (pinfunction "X_1") (pintype "passive"))
    )
    (net (code "107") (name "Net-(SUB-Y)") (class "Default")
      (node (ref "K19") (pin "3") (pinfunction "3_3") (pintype "passive"))
      (node (ref "SUB") (pin "2") (pinfunction "Y_2") (pintype "passive"))
    )
    (net (code "108") (name "Net-(U1-BOOT0)") (class "Default")
      (node (ref "R2") (pin "1") (pinfunction "1_1") (pintype "passive"))
      (node (ref "U1") (pin "60") (pinfunction "BOOT0_60") (pintype "input"))
    )
    (net (code "109") (name "Net-(U1-OSC_IN{slash}PD0)") (class "Default")
      (node (ref "U1") (pin "5") (pinfunction "OSC_IN/PD0_5") (pintype "input"))
      (node (ref "X1") (pin "1") (pinfunction "OSC1_1") (pintype "passive"))
    )
    (net (code "110") (name "Net-(U1-OSC_OUT{slash}PD1)") (class "Default")
      (node (ref "R1") (pin "2") (pinfunction "2_2") (pintype "passive"))
      (node (ref "U1") (pin "6") (pinfunction "OSC_OUT/PD1_6") (pintype "output"))
    )
    (net (code "111") (name "Net-(U2-BP)") (class "Default")
      (node (ref "C21") (pin "2") (pinfunction "2_2") (pintype "passive"))
      (node (ref "U2") (pin "4") (pinfunction "BP_4") (pintype "passive"))
    )
    (net (code "112") (name "Net-(U3-Vref)") (class "Default")
      (node (ref "C76") (pin "1") (pinfunction "1_1") (pintype "passive"))
      (node (ref "U3") (pin "1") (pinfunction "Vref_1") (pintype "passive"))
    )
    (net (code "113") (name "Net-(U4-Vref)") (class "Default")
      (node (ref "C73") (pin "1") (pinfunction "1_1") (pintype "passive"))
      (node (ref "U4") (pin "1") (pinfunction "Vref_1") (pintype "passive"))
    )
    (net (code "114") (name "Net-(U5-Vout)") (class "Default")
      (node (ref "C91") (pin "2") (pinfunction "2_2") (pintype "passive"))
      (node (ref "U5") (pin "6") (pinfunction "Vout_6") (pintype "passive"))
      (node (ref "U6") (pin "3") (pinfunction "+IN_3") (pintype "passive"))
    )
    (net (code "115") (name "Net-(U7-IN+)") (class "Default")
      (node (ref "C80") (pin "1") (pinfunction "1_1") (pintype "passive"))
      (node (ref "R13") (pin "2") (pinfunction "2_2") (pintype "passive"))
      (node (ref "U7") (pin "3") (pinfunction "IN+_3") (pintype "passive"))
    )
    (net (code "116") (name "Net-(U19-Vout)") (class "Default")
      (node (ref "C92") (pin "2") (pinfunction "2_2") (pintype "passive"))
      (node (ref "U19") (pin "6") (pinfunction "Vout_6") (pintype "passive"))
      (node (ref "U26") (pin "3") (pinfunction "+IN_3") (pintype "passive"))
    )
    (net (code "117") (name "Net-(U22-+IN_A)") (class "Default")
      (node (ref "R16") (pin "2") (pinfunction "2_2") (pintype "passive"))
      (node (ref "R17") (pin "2") (pinfunction "2_2") (pintype "passive"))
      (node (ref "U22") (pin "3") (pinfunction "+IN_A_3") (pintype "input"))
    )
    (net (code "118") (name "Net-(U22--IN_A)") (class "Default")
      (node (ref "C40") (pin "1") (pinfunction "1_1") (pintype "passive"))
      (node (ref "R14") (pin "2") (pinfunction "2_2") (pintype "passive"))
      (node (ref "R15") (pin "1") (pinfunction "1_1") (pintype "passive"))
      (node (ref "U22") (pin "2") (pinfunction "-IN_A_2") (pintype "input"))
    )
    (net (code "119") (name "Net-(U23-+IN_A)") (class "Default")
      (node (ref "R22") (pin "2") (pinfunction "2_2") (pintype "passive"))
      (node (ref "R23") (pin "2") (pinfunction "2_2") (pintype "passive"))
      (node (ref "U23") (pin "3") (pinfunction "+IN_A_3") (pintype "input"))
    )
    (net (code "120") (name "Net-(U23--IN_A)") (class "Default")
      (node (ref "C39") (pin "1") (pinfunction "1_1") (pintype "passive"))
      (node (ref "R20") (pin "1") (pinfunction "1_1") (pintype "passive"))
      (node (ref "R21") (pin "2") (pinfunction "2_2") (pintype "passive"))
      (node (ref "U23") (pin "2") (pinfunction "-IN_A_2") (pintype "input"))
    )
    (net (code "121") (name "Net-(U24-IN+)") (class "Default")
      (node (ref "R90") (pin "1") (pinfunction "1_1") (pintype "passive"))
      (node (ref "R91") (pin "1") (pinfunction "1_1") (pintype "passive"))
      (node (ref "U24") (pin "1") (pinfunction "IN+_1") (pintype "passive"))
    )
    (net (code "122") (name "Net-(U24-OUT)") (class "Default")
      (node (ref "R8") (pin "1") (pinfunction "1_1") (pintype "passive"))
      (node (ref "U24") (pin "6") (pinfunction "OUT_6") (pintype "passive"))
    )
    (net (code "123") (name "Net-(U29-+IN_A)") (class "Default")
      (node (ref "R34") (pin "2") (pinfunction "2_2") (pintype "passive"))
      (node (ref "R35") (pin "2") (pinfunction "2_2") (pintype "passive"))
      (node (ref "U29") (pin "3") (pinfunction "+IN_A_3") (pintype "input"))
    )
    (net (code "124") (name "Net-(U29--IN_A)") (class "Default")
      (node (ref "C41") (pin "2") (pinfunction "2_2") (pintype "passive"))
      (node (ref "R18") (pin "2") (pinfunction "2_2") (pintype "passive"))
      (node (ref "R19") (pin "1") (pinfunction "1_1") (pintype "passive"))
      (node (ref "U29") (pin "2") (pinfunction "-IN_A_2") (pintype "input"))
    )
    (net (code "125") (name "Net-(U30-+IN_A)") (class "Default")
      (node (ref "R36") (pin "2") (pinfunction "2_2") (pintype "passive"))
      (node (ref "R37") (pin "2") (pinfunction "2_2") (pintype "passive"))
      (node (ref "U30") (pin "3") (pinfunction "+IN_A_3") (pintype "input"))
    )
    (net (code "126") (name "Net-(U30--IN_A)") (class "Default")
      (node (ref "C38") (pin "1") (pinfunction "1_1") (pintype "passive"))
      (node (ref "R24") (pin "2") (pinfunction "2_2") (pintype "passive"))
      (node (ref "R25") (pin "1") (pinfunction "1_1") (pintype "passive"))
      (node (ref "U30") (pin "2") (pinfunction "-IN_A_2") (pintype "input"))
    )
    (net (code "127") (name "Net-(U32-+IN_B)") (class "Default")
      (node (ref "K14") (pin "4") (pintype "passive"))
      (node (ref "R60") (pin "2") (pinfunction "2_2") (pintype "passive"))
      (node (ref "R61") (pin "1") (pinfunction "1_1") (pintype "passive"))
      (node (ref "U32") (pin "5") (pinfunction "+IN_B_5") (pintype "passive"))
    )
    (net (code "128") (name "Net-(U32--IN_A)") (class "Default")
      (node (ref "K14") (pin "6") (pintype "passive"))
      (node (ref "R60") (pin "1") (pinfunction "1_1") (pintype "passive"))
      (node (ref "U32") (pin "1") (pinfunction "Out_A_1") (pintype "passive"))
      (node (ref "U32") (pin "2") (pinfunction "-IN_A_2") (pintype "input"))
    )
    (net (code "129") (name "Net-(U32--IN_B)") (class "Default")
      (node (ref "R62") (pin "1") (pinfunction "1_1") (pintype "passive"))
      (node (ref "U32") (pin "6") (pinfunction "-IN_B_6") (pintype "passive"))
      (node (ref "U32") (pin "7") (pinfunction "Out_B_7") (pintype "passive"))
    )
    (net (code "130") (name "Net-(U33-+IN)") (class "Default")
      (node (ref "R62") (pin "2") (pinfunction "2_2") (pintype "passive"))
      (node (ref "R63") (pin "2") (pinfunction "2_2") (pintype "passive"))
      (node (ref "U33") (pin "3") (pinfunction "+IN_3") (pintype "passive"))
    )
    (net (code "131") (name "Net-(U33--IN)") (class "Default")
      (node (ref "C128") (pin "2") (pinfunction "2_2") (pintype "passive"))
      (node (ref "R64") (pin "1") (pinfunction "1_1") (pintype "passive"))
      (node (ref "R65") (pin "2") (pinfunction "2_2") (pintype "passive"))
      (node (ref "U33") (pin "2") (pinfunction "-IN_2") (pintype "passive"))
    )
    (net (code "132") (name "Net-(U33-OUT)") (class "Default")
      (node (ref "C128") (pin "1") (pinfunction "1_1") (pintype "passive"))
      (node (ref "R65") (pin "1") (pinfunction "1_1") (pintype "passive"))
      (node (ref "R66") (pin "2") (pinfunction "2_2") (pintype "passive"))
      (node (ref "U33") (pin "6") (pinfunction "OUT_6") (pintype "passive"))
    )
    (net (code "133") (name "Net-(U34-AIN+)") (class "Default")
      (node (ref "C131") (pin "2") (pinfunction "2_2") (pintype "passive"))
      (node (ref "R66") (pin "1") (pinfunction "1_1") (pintype "passive"))
      (node (ref "U34") (pin "3") (pinfunction "AIN+_3") (pintype "passive"))
    )
    (net (code "134") (name "Net-(U35-+IN_B)") (class "Default")
      (node (ref "K15") (pin "4") (pintype "passive"))
      (node (ref "R67") (pin "2") (pinfunction "2_2") (pintype "passive"))
      (node (ref "R68") (pin "1") (pinfunction "1_1") (pintype "passive"))
      (node (ref "U35") (pin "5") (pinfunction "+IN_B_5") (pintype "passive"))
    )
    (net (code "135") (name "Net-(U35--IN_A)") (class "Default")
      (node (ref "K15") (pin "6") (pintype "passive"))
      (node (ref "R67") (pin "1") (pinfunction "1_1") (pintype "passive"))
      (node (ref "U35") (pin "1") (pinfunction "Out_A_1") (pintype "passive"))
      (node (ref "U35") (pin "2") (pinfunction "-IN_A_2") (pintype "input"))
    )
    (net (code "136") (name "Net-(U35--IN_B)") (class "Default")
      (node (ref "R69") (pin "1") (pinfunction "1_1") (pintype "passive"))
      (node (ref "U35") (pin "6") (pinfunction "-IN_B_6") (pintype "passive"))
      (node (ref "U35") (pin "7") (pinfunction "Out_B_7") (pintype "passive"))
    )
    (net (code "137") (name "Net-(U36-+IN)") (class "Default")
      (node (ref "R69") (pin "2") (pinfunction "2_2") (pintype "passive"))
      (node (ref "R70") (pin "2") (pinfunction "2_2") (pintype "passive"))
      (node (ref "U36") (pin "3") (pinfunction "+IN_3") (pintype "passive"))
    )
    (net (code "138") (name "Net-(U36--IN)") (class "Default")
      (node (ref "C142") (pin "2") (pinfunction "2_2") (pintype "passive"))
      (node (ref "R71") (pin "1") (pinfunction "1_1") (pintype "passive"))
      (node (ref "R72") (pin "2") (pinfunction "2_2") (pintype "passive"))
      (node (ref "U36") (pin "2") (pinfunction "-IN_2") (pintype "passive"))
    )
    (net (code "139") (name "Net-(U36-OUT)") (class "Default")
      (node (ref "C142") (pin "1") (pinfunction "1_1") (pintype "passive"))
      (node (ref "R72") (pin "1") (pinfunction "1_1") (pintype "passive"))
      (node (ref "R73") (pin "2") (pinfunction "2_2") (pintype "passive"))
      (node (ref "U36") (pin "6") (pinfunction "OUT_6") (pintype "passive"))
    )
    (net (code "140") (name "Net-(U37-AIN+)") (class "Default")
      (node (ref "C138") (pin "2") (pinfunction "2_2") (pintype "passive"))
      (node (ref "R73") (pin "1") (pinfunction "1_1") (pintype "passive"))
      (node (ref "U37") (pin "3") (pinfunction "AIN+_3") (pintype "passive"))
    )
    (net (code "141") (name "Net-(U38-+IN_B)") (class "Default")
      (node (ref "K16") (pin "4") (pintype "passive"))
      (node (ref "R74") (pin "2") (pinfunction "2_2") (pintype "passive"))
      (node (ref "R75") (pin "1") (pinfunction "1_1") (pintype "passive"))
      (node (ref "U38") (pin "5") (pinfunction "+IN_B_5") (pintype "passive"))
    )
    (net (code "142") (name "Net-(U38--IN_A)") (class "Default")
      (node (ref "K16") (pin "6") (pintype "passive"))
      (node (ref "R74") (pin "1") (pinfunction "1_1") (pintype "passive"))
      (node (ref "U38") (pin "1") (pinfunction "Out_A_1") (pintype "passive"))
      (node (ref "U38") (pin "2") (pinfunction "-IN_A_2") (pintype "input"))
    )
    (net (code "143") (name "Net-(U38--IN_B)") (class "Default")
      (node (ref "R76") (pin "1") (pinfunction "1_1") (pintype "passive"))
      (node (ref "U38") (pin "6") (pinfunction "-IN_B_6") (pintype "passive"))
      (node (ref "U38") (pin "7") (pinfunction "Out_B_7") (pintype "passive"))
    )
    (net (code "144") (name "Net-(U39-+IN)") (class "Default")
      (node (ref "R76") (pin "2") (pinfunction "2_2") (pintype "passive"))
      (node (ref "R77") (pin "2") (pinfunction "2_2") (pintype "passive"))
      (node (ref "U39") (pin "3") (pinfunction "+IN_3") (pintype "passive"))
    )
    (net (code "145") (name "Net-(U39--IN)") (class "Default")
      (node (ref "C158") (pin "2") (pinfunction "2_2") (pintype "passive"))
      (node (ref "R78") (pin "1") (pinfunction "1_1") (pintype "passive"))
      (node (ref "R79") (pin "2") (pinfunction "2_2") (pintype "passive"))
      (node (ref "U39") (pin "2") (pinfunction "-IN_2") (pintype "passive"))
    )
    (net (code "146") (name "Net-(U39-OUT)") (class "Default")
      (node (ref "C158") (pin "1") (pinfunction "1_1") (pintype "passive"))
      (node (ref "R79") (pin "1") (pinfunction "1_1") (pintype "passive"))
      (node (ref "R80") (pin "2") (pinfunction "2_2") (pintype "passive"))
      (node (ref "U39") (pin "6") (pinfunction "OUT_6") (pintype "passive"))
    )
    (net (code "147") (name "Net-(U40-AIN+)") (class "Default")
      (node (ref "C149") (pin "2") (pinfunction "2_2") (pintype "passive"))
      (node (ref "R80") (pin "1") (pinfunction "1_1") (pintype "passive"))
      (node (ref "U40") (pin "3") (pinfunction "AIN+_3") (pintype "passive"))
    )
    (net (code "148") (name "Net-(U41-+IN_B)") (class "Default")
      (node (ref "K17") (pin "4") (pintype "passive"))
      (node (ref "R81") (pin "2") (pinfunction "2_2") (pintype "passive"))
      (node (ref "R82") (pin "1") (pinfunction "1_1") (pintype "passive"))
      (node (ref "U41") (pin "5") (pinfunction "+IN_B_5") (pintype "passive"))
    )
    (net (code "149") (name "Net-(U41--IN_A)") (class "Default")
      (node (ref "K17") (pin "6") (pintype "passive"))
      (node (ref "R81") (pin "1") (pinfunction "1_1") (pintype "passive"))
      (node (ref "U41") (pin "1") (pinfunction "Out_A_1") (pintype "passive"))
      (node (ref "U41") (pin "2") (pinfunction "-IN_A_2") (pintype "input"))
    )
    (net (code "150") (name "Net-(U41--IN_B)") (class "Default")
      (node (ref "R83") (pin "1") (pinfunction "1_1") (pintype "passive"))
      (node (ref "U41") (pin "6") (pinfunction "-IN_B_6") (pintype "passive"))
      (node (ref "U41") (pin "7") (pinfunction "Out_B_7") (pintype "passive"))
    )
    (net (code "151") (name "Net-(U42-+IN)") (class "Default")
      (node (ref "R83") (pin "2") (pinfunction "2_2") (pintype "passive"))
      (node (ref "R84") (pin "2") (pinfunction "2_2") (pintype "passive"))
      (node (ref "U42") (pin "3") (pinfunction "+IN_3") (pintype "passive"))
    )
    (net (code "152") (name "Net-(U42--IN)") (class "Default")
      (node (ref "C159") (pin "2") (pinfunction "2_2") (pintype "passive"))
      (node (ref "R85") (pin "1") (pinfunction "1_1") (pintype "passive"))
      (node (ref "R86") (pin "2") (pinfunction "2_2") (pintype "passive"))
      (node (ref "U42") (pin "2") (pinfunction "-IN_2") (pintype "passive"))
    )
    (net (code "153") (name "Net-(U42-OUT)") (class "Default")
      (node (ref "C159") (pin "1") (pinfunction "1_1") (pintype "passive"))
      (node (ref "R86") (pin "1") (pinfunction "1_1") (pintype "passive"))
      (node (ref "R87") (pin "2") (pinfunction "2_2") (pintype "passive"))
      (node (ref "U42") (pin "6") (pinfunction "OUT_6") (pintype "passive"))
    )
    (net (code "154") (name "Net-(U43-AIN+)") (class "Default")
      (node (ref "C161") (pin "2") (pinfunction "2_2") (pintype "passive"))
      (node (ref "R87") (pin "1") (pinfunction "1_1") (pintype "passive"))
      (node (ref "U43") (pin "3") (pinfunction "AIN+_3") (pintype "passive"))
    )
    (net (code "155") (name "Net-(U44-A)") (class "Default")
      (node (ref "J1") (pin "3") (pinfunction "3_3") (pintype "passive"))
      (node (ref "R100") (pin "2") (pinfunction "2_2") (pintype "passive"))
      (node (ref "R102") (pin "1") (pinfunction "1_1") (pintype "passive"))
      (node (ref "U44") (pin "6") (pinfunction "A_6") (pintype "passive"))
    )
    (net (code "156") (name "Net-(U44-B)") (class "Default")
      (node (ref "J1") (pin "2") (pinfunction "2_2") (pintype "passive"))
      (node (ref "R100") (pin "1") (pinfunction "1_1") (pintype "passive"))
      (node (ref "R101") (pin "1") (pinfunction "1_1") (pintype "passive"))
      (node (ref "U44") (pin "7") (pinfunction "B_7") (pintype "passive"))
    )
    (net (code "157") (name "Net-(U45-A)") (class "Default")
      (node (ref "R103") (pin "2") (pinfunction "2_2") (pintype "passive"))
      (node (ref "R105") (pin "1") (pinfunction "1_1") (pintype "passive"))
      (node (ref "RS485_2") (pin "2") (pinfunction "2_2") (pintype "passive"))
      (node (ref "U45") (pin "6") (pinfunction "A_6") (pintype "passive"))
    )
    (net (code "158") (name "Net-(U45-B)") (class "Default")
      (node (ref "R103") (pin "1") (pinfunction "1_1") (pintype "passive"))
      (node (ref "R104") (pin "1") (pinfunction "1_1") (pintype "passive"))
      (node (ref "RS485_2") (pin "1") (pinfunction "1_1") (pintype "passive"))
      (node (ref "U45") (pin "7") (pinfunction "B_7") (pintype "passive"))
    )
    (net (code "159") (name "Net-(USB-D+)") (class "Default")
      (node (ref "R41") (pin "1") (pinfunction "1_1") (pintype "passive"))
      (node (ref "USB") (pin "3") (pinfunction "D+_3") (pintype "passive"))
    )
    (net (code "160") (name "Net-(USB-D-)") (class "Default")
      (node (ref "R40") (pin "1") (pinfunction "1_1") (pintype "passive"))
      (node (ref "USB") (pin "2") (pinfunction "D-_2") (pintype "passive"))
    )
    (net (code "161") (name "Net-(X1-OSC2)") (class "Default")
      (node (ref "R1") (pin "1") (pinfunction "1_1") (pintype "passive"))
      (node (ref "X1") (pin "3") (pinfunction "OSC2_3") (pintype "passive"))
    )
    (net (code "162") (name "unconnected-(DL-Vcc-Pad1)") (class "Default")
      (node (ref "DL") (pin "1") (pinfunction "Vcc_1") (pintype "passive"))
    )
    (net (code "163") (name "unconnected-(J1-MH1-Pad10)") (class "Default")
      (node (ref "J1") (pin "10") (pinfunction "MH1_10") (pintype "passive"))
    )
    (net (code "164") (name "unconnected-(J1-MH2-Pad11)") (class "Default")
      (node (ref "J1") (pin "11") (pinfunction "MH2_11") (pintype "passive"))
    )
    (net (code "165") (name "unconnected-(J1-Pad1)") (class "Default")
      (node (ref "J1") (pin "1") (pinfunction "1_1") (pintype "passive"))
    )
    (net (code "166") (name "unconnected-(J1-Pad4)") (class "Default")
      (node (ref "J1") (pin "4") (pinfunction "4_4") (pintype "passive"))
    )
    (net (code "167") (name "unconnected-(J1-Pad5)") (class "Default")
      (node (ref "J1") (pin "5") (pinfunction "5_5") (pintype "passive"))
    )
    (net (code "168") (name "unconnected-(J1-Pad6)") (class "Default")
      (node (ref "J1") (pin "6") (pinfunction "6_6") (pintype "passive"))
    )
    (net (code "169") (name "unconnected-(J1-Pad7)") (class "Default")
      (node (ref "J1") (pin "7") (pinfunction "7_7") (pintype "passive"))
    )
    (net (code "170") (name "unconnected-(J1-Pad8)") (class "Default")
      (node (ref "J1") (pin "8") (pinfunction "8_8") (pintype "passive"))
    )
    (net (code "171") (name "unconnected-(J1-Pad9)") (class "Default")
      (node (ref "J1") (pin "9") (pinfunction "9_9") (pintype "passive"))
    )
    (net (code "172") (name "unconnected-(K1-Pad1)") (class "Default")
      (node (ref "K1") (pin "1") (pintype "passive"))
    )
    (net (code "173") (name "unconnected-(K1-Pad3)") (class "Default")
      (node (ref "K1") (pin "3") (pintype "passive"))
    )
    (net (code "174") (name "unconnected-(K2-Pad1)") (class "Default")
      (node (ref "K2") (pin "1") (pintype "passive"))
    )
    (net (code "175") (name "unconnected-(K2-Pad3)") (class "Default")
      (node (ref "K2") (pin "3") (pintype "passive"))
    )
    (net (code "176") (name "unconnected-(K3-Pad1)") (class "Default")
      (node (ref "K3") (pin "1") (pintype "passive"))
    )
    (net (code "177") (name "unconnected-(K3-Pad3)") (class "Default")
      (node (ref "K3") (pin "3") (pintype "passive"))
    )
    (net (code "178") (name "unconnected-(K4-Pad1)") (class "Default")
      (node (ref "K4") (pin "1") (pintype "passive"))
    )
    (net (code "179") (name "unconnected-(K4-Pad3)") (class "Default")
      (node (ref "K4") (pin "3") (pintype "passive"))
    )
    (net (code "180") (name "unconnected-(K9-Pad1)") (class "Default")
      (node (ref "K9") (pin "1") (pintype "passive"))
    )
    (net (code "181") (name "unconnected-(K9-Pad3)") (class "Default")
      (node (ref "K9") (pin "3") (pintype "passive"))
    )
    (net (code "182") (name "unconnected-(K10-Pad1)") (class "Default")
      (node (ref "K10") (pin "1") (pintype "passive"))
    )
    (net (code "183") (name "unconnected-(K10-Pad3)") (class "Default")
      (node (ref "K10") (pin "3") (pintype "passive"))
    )
    (net (code "184") (name "unconnected-(K11-Pad1)") (class "Default")
      (node (ref "K11") (pin "1") (pintype "passive"))
    )
    (net (code "185") (name "unconnected-(K11-Pad3)") (class "Default")
      (node (ref "K11") (pin "3") (pintype "passive"))
    )
    (net (code "186") (name "unconnected-(K12-Pad1)") (class "Default")
      (node (ref "K12") (pin "1") (pintype "passive"))
    )
    (net (code "187") (name "unconnected-(K12-Pad3)") (class "Default")
      (node (ref "K12") (pin "3") (pintype "passive"))
    )
    (net (code "188") (name "unconnected-(K13-Pad1)") (class "Default")
      (node (ref "K13") (pin "1") (pintype "passive"))
    )
    (net (code "189") (name "unconnected-(K13-Pad3)") (class "Default")
      (node (ref "K13") (pin "3") (pintype "passive"))
    )
    (net (code "190") (name "unconnected-(K14-Pad1)") (class "Default")
      (node (ref "K14") (pin "1") (pintype "passive"))
    )
    (net (code "191") (name "unconnected-(K14-Pad3)") (class "Default")
      (node (ref "K14") (pin "3") (pintype "passive"))
    )
    (net (code "192") (name "unconnected-(K15-Pad1)") (class "Default")
      (node (ref "K15") (pin "1") (pintype "passive"))
    )
    (net (code "193") (name "unconnected-(K15-Pad3)") (class "Default")
      (node (ref "K15") (pin "3") (pintype "passive"))
    )
    (net (code "194") (name "unconnected-(K16-Pad1)") (class "Default")
      (node (ref "K16") (pin "1") (pintype "passive"))
    )
    (net (code "195") (name "unconnected-(K16-Pad3)") (class "Default")
      (node (ref "K16") (pin "3") (pintype "passive"))
    )
    (net (code "196") (name "unconnected-(K17-Pad1)") (class "Default")
      (node (ref "K17") (pin "1") (pintype "passive"))
    )
    (net (code "197") (name "unconnected-(K17-Pad3)") (class "Default")
      (node (ref "K17") (pin "3") (pintype "passive"))
    )
    (net (code "198") (name "unconnected-(K18-Pad2)") (class "Default")
      (node (ref "K18") (pin "2") (pinfunction "2_2") (pintype "passive"))
    )
    (net (code "199") (name "unconnected-(K18-Pad7)") (class "Default")
      (node (ref "K18") (pin "7") (pinfunction "7_7") (pintype "passive"))
    )
    (net (code "200") (name "unconnected-(K19-Pad2)") (class "Default")
      (node (ref "K19") (pin "2") (pinfunction "2_2") (pintype "passive"))
    )
    (net (code "201") (name "unconnected-(K19-Pad7)") (class "Default")
      (node (ref "K19") (pin "7") (pinfunction "7_7") (pintype "passive"))
    )
    (net (code "202") (name "unconnected-(K20-Pad2)") (class "Default")
      (node (ref "K20") (pin "2") (pinfunction "2_2") (pintype "passive"))
    )
    (net (code "203") (name "unconnected-(K20-Pad7)") (class "Default")
      (node (ref "K20") (pin "7") (pinfunction "7_7") (pintype "passive"))
    )
    (net (code "204") (name "unconnected-(LCD-Pad6)") (class "Default")
      (node (ref "LCD") (pin "6") (pinfunction "6_6") (pintype "passive+no_connect"))
    )
    (net (code "205") (name "unconnected-(U1-NRST-Pad7)") (class "Default")
      (node (ref "U1") (pin "7") (pinfunction "NRST_7") (pintype "bidirectional"))
    )
    (net (code "206") (name "unconnected-(U3-NC-Pad2)") (class "Default")
      (node (ref "U3") (pin "2") (pinfunction "NC_2") (pintype "passive+no_connect"))
    )
    (net (code "207") (name "unconnected-(U3-NC-Pad6)") (class "Default")
      (node (ref "U3") (pin "6") (pinfunction "NC_6") (pintype "passive+no_connect"))
    )
    (net (code "208") (name "unconnected-(U3-SDO-Pad8)") (class "Default")
      (node (ref "U3") (pin "8") (pinfunction "SDO_8") (pintype "passive+no_connect"))
    )
    (net (code "209") (name "unconnected-(U4-NC-Pad2)") (class "Default")
      (node (ref "U4") (pin "2") (pinfunction "NC_2") (pintype "passive+no_connect"))
    )
    (net (code "210") (name "unconnected-(U4-NC-Pad6)") (class "Default")
      (node (ref "U4") (pin "6") (pinfunction "NC_6") (pintype "passive+no_connect"))
    )
    (net (code "211") (name "unconnected-(U4-SDO-Pad8)") (class "Default")
      (node (ref "U4") (pin "8") (pinfunction "SDO_8") (pintype "passive+no_connect"))
    )
    (net (code "212") (name "unconnected-(U5-NC-Pad3)") (class "Default")
      (node (ref "U5") (pin "3") (pinfunction "NC_3") (pintype "passive+no_connect"))
    )
    (net (code "213") (name "unconnected-(U5-NC-Pad7)") (class "Default")
      (node (ref "U5") (pin "7") (pinfunction "NC_7") (pintype "passive"))
    )
    (net (code "214") (name "unconnected-(U5-TP-Pad1)") (class "Default")
      (node (ref "U5") (pin "1") (pinfunction "TP_1") (pintype "passive+no_connect"))
    )
    (net (code "215") (name "unconnected-(U5-TP-Pad8)") (class "Default")
      (node (ref "U5") (pin "8") (pinfunction "TP_8") (pintype "passive+no_connect"))
    )
    (net (code "216") (name "unconnected-(U5-TRIM-Pad5)") (class "Default")
      (node (ref "U5") (pin "5") (pinfunction "TRIM_5") (pintype "passive+no_connect"))
    )
    (net (code "217") (name "unconnected-(U9-NC-Pad1)") (class "Default")
      (node (ref "U9") (pin "1") (pinfunction "NC_1") (pintype "passive"))
    )
    (net (code "218") (name "unconnected-(U9-NC-Pad5)") (class "Default")
      (node (ref "U9") (pin "5") (pinfunction "NC_5") (pintype "passive"))
    )
    (net (code "219") (name "unconnected-(U9-NC-Pad6)") (class "Default")
      (node (ref "U9") (pin "6") (pinfunction "NC_6") (pintype "passive"))
    )
    (net (code "220") (name "unconnected-(U19-NC-Pad3)") (class "Default")
      (node (ref "U19") (pin "3") (pinfunction "NC_3") (pintype "passive+no_connect"))
    )
    (net (code "221") (name "unconnected-(U19-NC-Pad7)") (class "Default")
      (node (ref "U19") (pin "7") (pinfunction "NC_7") (pintype "passive+no_connect"))
    )
    (net (code "222") (name "unconnected-(U19-TP-Pad1)") (class "Default")
      (node (ref "U19") (pin "1") (pinfunction "TP_1") (pintype "passive"))
    )
    (net (code "223") (name "unconnected-(U19-TP-Pad8)") (class "Default")
      (node (ref "U19") (pin "8") (pinfunction "TP_8") (pintype "passive"))
    )
    (net (code "224") (name "unconnected-(U19-TRIM-Pad5)") (class "Default")
      (node (ref "U19") (pin "5") (pinfunction "TRIM_5") (pintype "passive+no_connect"))
    )
    (net (code "225") (name "unconnected-(U24-IC-Pad3)") (class "Default")
      (node (ref "U24") (pin "3") (pinfunction "IC_3") (pintype "passive+no_connect"))
    )
    (net (code "226") (name "unconnected-(U29--IN_B-Pad6)") (class "Default")
      (node (ref "U29") (pin "6") (pinfunction "-IN_B_6") (pintype "passive"))
    )
    (net (code "227") (name "unconnected-(U29-Out_B-Pad7)") (class "Default")
      (node (ref "U29") (pin "7") (pinfunction "Out_B_7") (pintype "passive"))
    )
    (net (code "228") (name "unconnected-(U33-NC-Pad5)") (class "Default")
      (node (ref "U33") (pin "5") (pinfunction "NC_5") (pintype "passive"))
    )
    (net (code "229") (name "unconnected-(U33-TRIM-Pad1)") (class "Default")
      (node (ref "U33") (pin "1") (pinfunction "TRIM_1") (pintype "passive"))
    )
    (net (code "230") (name "unconnected-(U33-TRIM-Pad8)") (class "Default")
      (node (ref "U33") (pin "8") (pinfunction "TRIM_8") (pintype "passive"))
    )
    (net (code "231") (name "unconnected-(U36-NC-Pad5)") (class "Default")
      (node (ref "U36") (pin "5") (pinfunction "NC_5") (pintype "passive"))
    )
    (net (code "232") (name "unconnected-(U36-TRIM-Pad1)") (class "Default")
      (node (ref "U36") (pin "1") (pinfunction "TRIM_1") (pintype "passive"))
    )
    (net (code "233") (name "unconnected-(U36-TRIM-Pad8)") (class "Default")
      (node (ref "U36") (pin "8") (pinfunction "TRIM_8") (pintype "passive"))
    )
    (net (code "234") (name "unconnected-(U39-NC-Pad5)") (class "Default")
      (node (ref "U39") (pin "5") (pinfunction "NC_5") (pintype "passive"))
    )
    (net (code "235") (name "unconnected-(U39-TRIM-Pad1)") (class "Default")
      (node (ref "U39") (pin "1") (pinfunction "TRIM_1") (pintype "passive"))
    )
    (net (code "236") (name "unconnected-(U39-TRIM-Pad8)") (class "Default")
      (node (ref "U39") (pin "8") (pinfunction "TRIM_8") (pintype "passive"))
    )
    (net (code "237") (name "unconnected-(U42-NC-Pad5)") (class "Default")
      (node (ref "U42") (pin "5") (pinfunction "NC_5") (pintype "passive"))
    )
    (net (code "238") (name "unconnected-(U42-TRIM-Pad1)") (class "Default")
      (node (ref "U42") (pin "1") (pinfunction "TRIM_1") (pintype "passive"))
    )
    (net (code "239") (name "unconnected-(U42-TRIM-Pad8)") (class "Default")
      (node (ref "U42") (pin "8") (pinfunction "TRIM_8") (pintype "passive"))
    )
    (net (code "240") (name "unconnected-(USB-Vcc-Pad1)") (class "Default")
      (node (ref "USB") (pin "1") (pinfunction "Vcc_1") (pintype "passive"))
    )
  )
)
